# SignalRouting.net
KiCad netlist of a schematic drawn in Altium Designer
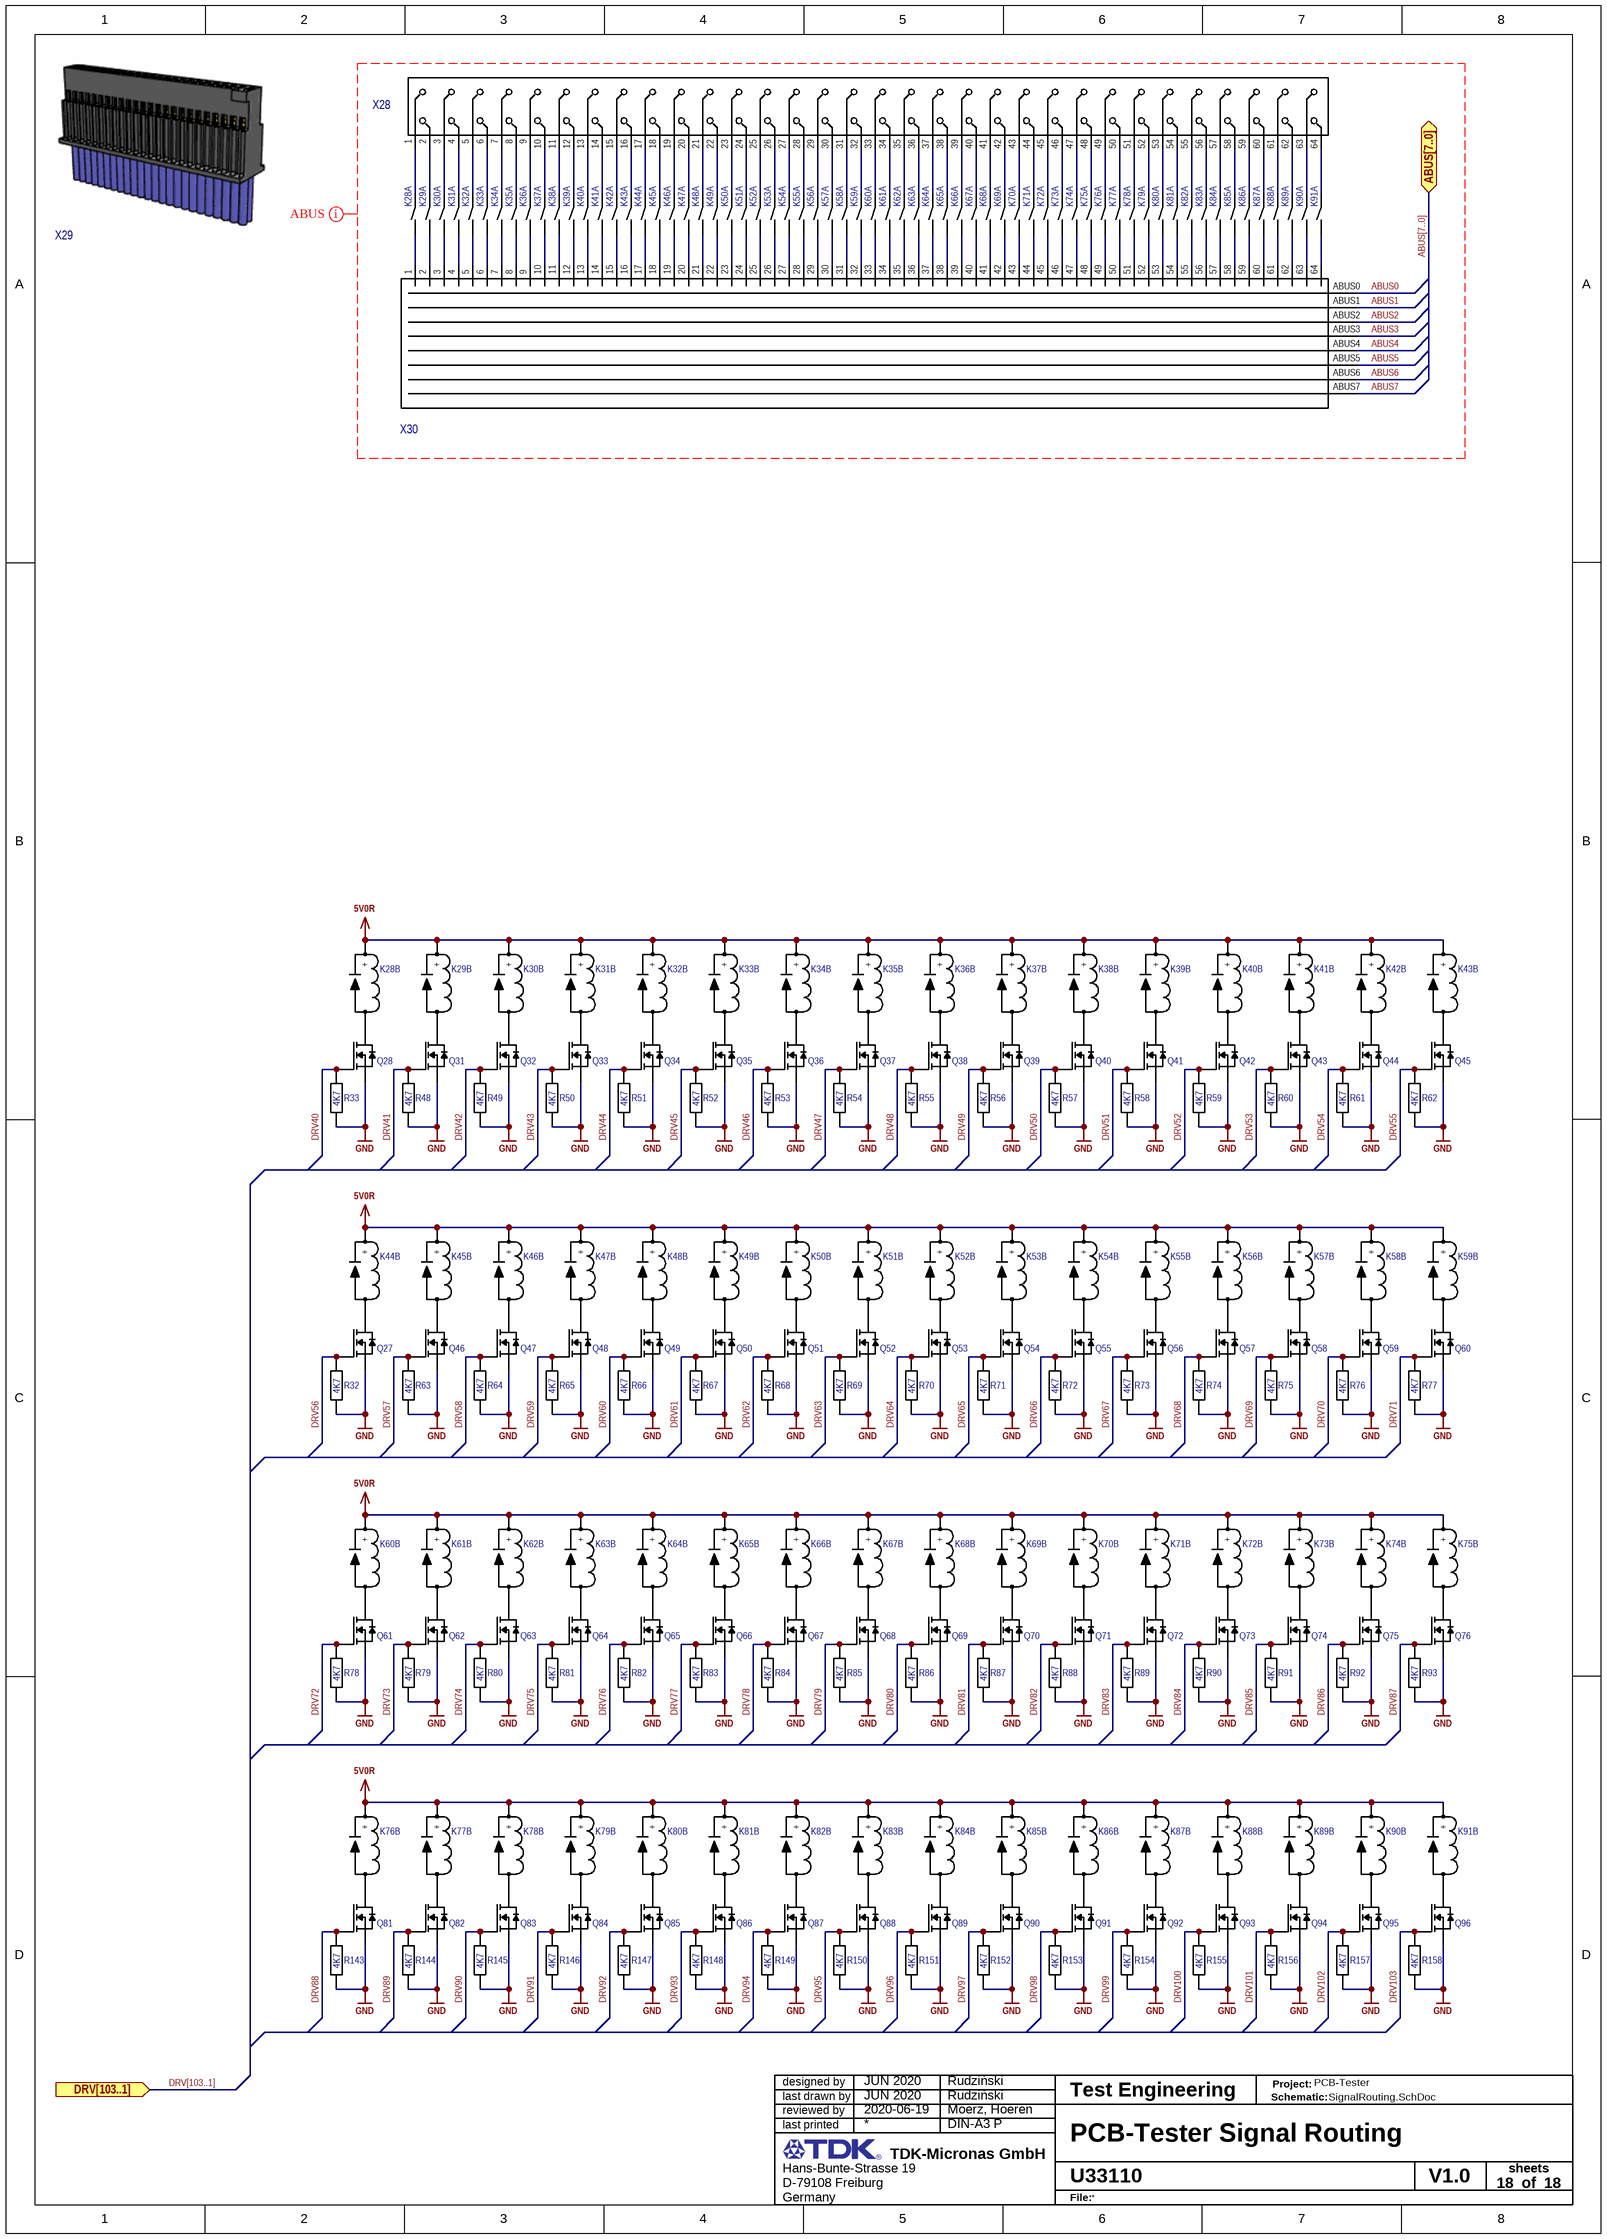
[diagram p0: SignalRouting.SchDoc]

(export (version "E")
  (design (tool "Eeschema 10.0.6"))
  (components
    (comp (ref "K28")
      (value "K")
      (footprint "118-1A")
      (description "5V Signal Relais, Normal Open")
      (fields
        (field (name "02. DISTRIBUTOR PART NUMBER") "118-1-A-5/2D")
        (field (name "13. CREATED DATE/NAME") "20.12.17 S. Kaiser")
      )
      (libsource (lib "chickenfood") (part "118-1-A-5/2D"))
    )
    (comp (ref "K29")
      (value "K")
      (footprint "118-1A")
      (description "5V Signal Relais, Normal Open")
      (fields
        (field (name "02. DISTRIBUTOR PART NUMBER") "118-1-A-5/2D")
        (field (name "13. CREATED DATE/NAME") "20.12.17 S. Kaiser")
      )
      (libsource (lib "chickenfood") (part "118-1-A-5/2D"))
    )
    (comp (ref "K30")
      (value "K")
      (footprint "118-1A")
      (description "5V Signal Relais, Normal Open")
      (fields
        (field (name "02. DISTRIBUTOR PART NUMBER") "118-1-A-5/2D")
        (field (name "13. CREATED DATE/NAME") "20.12.17 S. Kaiser")
      )
      (libsource (lib "chickenfood") (part "118-1-A-5/2D"))
    )
    (comp (ref "K31")
      (value "K")
      (footprint "118-1A")
      (description "5V Signal Relais, Normal Open")
      (fields
        (field (name "02. DISTRIBUTOR PART NUMBER") "118-1-A-5/2D")
        (field (name "13. CREATED DATE/NAME") "20.12.17 S. Kaiser")
      )
      (libsource (lib "") (part "118-1-A-5/2D_1"))
    )
    (comp (ref "K32")
      (value "K")
      (footprint "118-1A")
      (description "5V Signal Relais, Normal Open")
      (fields
        (field (name "02. DISTRIBUTOR PART NUMBER") "118-1-A-5/2D")
        (field (name "13. CREATED DATE/NAME") "20.12.17 S. Kaiser")
      )
      (libsource (lib "") (part "118-1-A-5/2D_1"))
    )
    (comp (ref "K33")
      (value "K")
      (footprint "118-1A")
      (description "5V Signal Relais, Normal Open")
      (fields
        (field (name "02. DISTRIBUTOR PART NUMBER") "118-1-A-5/2D")
        (field (name "13. CREATED DATE/NAME") "20.12.17 S. Kaiser")
      )
      (libsource (lib "") (part "118-1-A-5/2D_1"))
    )
    (comp (ref "K34")
      (value "K")
      (footprint "118-1A")
      (description "5V Signal Relais, Normal Open")
      (fields
        (field (name "02. DISTRIBUTOR PART NUMBER") "118-1-A-5/2D")
        (field (name "13. CREATED DATE/NAME") "20.12.17 S. Kaiser")
      )
      (libsource (lib "chickenfood") (part "118-1-A-5/2D"))
    )
    (comp (ref "K35")
      (value "K")
      (footprint "118-1A")
      (description "5V Signal Relais, Normal Open")
      (fields
        (field (name "02. DISTRIBUTOR PART NUMBER") "118-1-A-5/2D")
        (field (name "13. CREATED DATE/NAME") "20.12.17 S. Kaiser")
      )
      (libsource (lib "chickenfood") (part "118-1-A-5/2D"))
    )
    (comp (ref "K36")
      (value "K")
      (footprint "118-1A")
      (description "5V Signal Relais, Normal Open")
      (fields
        (field (name "02. DISTRIBUTOR PART NUMBER") "118-1-A-5/2D")
        (field (name "13. CREATED DATE/NAME") "20.12.17 S. Kaiser")
      )
      (libsource (lib "chickenfood") (part "118-1-A-5/2D"))
    )
    (comp (ref "K37")
      (value "K")
      (footprint "118-1A")
      (description "5V Signal Relais, Normal Open")
      (fields
        (field (name "02. DISTRIBUTOR PART NUMBER") "118-1-A-5/2D")
        (field (name "13. CREATED DATE/NAME") "20.12.17 S. Kaiser")
      )
      (libsource (lib "chickenfood") (part "118-1-A-5/2D"))
    )
    (comp (ref "K38")
      (value "K")
      (footprint "118-1A")
      (description "5V Signal Relais, Normal Open")
      (fields
        (field (name "02. DISTRIBUTOR PART NUMBER") "118-1-A-5/2D")
        (field (name "13. CREATED DATE/NAME") "20.12.17 S. Kaiser")
      )
      (libsource (lib "chickenfood") (part "118-1-A-5/2D"))
    )
    (comp (ref "K39")
      (value "K")
      (footprint "118-1A")
      (description "5V Signal Relais, Normal Open")
      (fields
        (field (name "02. DISTRIBUTOR PART NUMBER") "118-1-A-5/2D")
        (field (name "13. CREATED DATE/NAME") "20.12.17 S. Kaiser")
      )
      (libsource (lib "chickenfood") (part "118-1-A-5/2D"))
    )
    (comp (ref "K40")
      (value "K")
      (footprint "118-1A")
      (description "5V Signal Relais, Normal Open")
      (fields
        (field (name "02. DISTRIBUTOR PART NUMBER") "118-1-A-5/2D")
        (field (name "13. CREATED DATE/NAME") "20.12.17 S. Kaiser")
      )
      (libsource (lib "chickenfood") (part "118-1-A-5/2D"))
    )
    (comp (ref "K41")
      (value "K")
      (footprint "118-1A")
      (description "5V Signal Relais, Normal Open")
      (fields
        (field (name "02. DISTRIBUTOR PART NUMBER") "118-1-A-5/2D")
        (field (name "13. CREATED DATE/NAME") "20.12.17 S. Kaiser")
      )
      (libsource (lib "chickenfood") (part "118-1-A-5/2D"))
    )
    (comp (ref "K42")
      (value "K")
      (footprint "118-1A")
      (description "5V Signal Relais, Normal Open")
      (fields
        (field (name "02. DISTRIBUTOR PART NUMBER") "118-1-A-5/2D")
        (field (name "13. CREATED DATE/NAME") "20.12.17 S. Kaiser")
      )
      (libsource (lib "") (part "118-1-A-5/2D_1"))
    )
    (comp (ref "K43")
      (value "K")
      (footprint "118-1A")
      (description "5V Signal Relais, Normal Open")
      (fields
        (field (name "02. DISTRIBUTOR PART NUMBER") "118-1-A-5/2D")
        (field (name "13. CREATED DATE/NAME") "20.12.17 S. Kaiser")
      )
      (libsource (lib "chickenfood") (part "118-1-A-5/2D"))
    )
    (comp (ref "K44")
      (value "K")
      (footprint "118-1A")
      (description "5V Signal Relais, Normal Open")
      (fields
        (field (name "02. DISTRIBUTOR PART NUMBER") "118-1-A-5/2D")
        (field (name "13. CREATED DATE/NAME") "20.12.17 S. Kaiser")
      )
      (libsource (lib "") (part "118-1-A-5/2D_1"))
    )
    (comp (ref "K45")
      (value "K")
      (footprint "118-1A")
      (description "5V Signal Relais, Normal Open")
      (fields
        (field (name "02. DISTRIBUTOR PART NUMBER") "118-1-A-5/2D")
        (field (name "13. CREATED DATE/NAME") "20.12.17 S. Kaiser")
      )
      (libsource (lib "chickenfood") (part "118-1-A-5/2D"))
    )
    (comp (ref "K46")
      (value "K")
      (footprint "118-1A")
      (description "5V Signal Relais, Normal Open")
      (fields
        (field (name "02. DISTRIBUTOR PART NUMBER") "118-1-A-5/2D")
        (field (name "13. CREATED DATE/NAME") "20.12.17 S. Kaiser")
      )
      (libsource (lib "") (part "118-1-A-5/2D_1"))
    )
    (comp (ref "K47")
      (value "K")
      (footprint "118-1A")
      (description "5V Signal Relais, Normal Open")
      (fields
        (field (name "02. DISTRIBUTOR PART NUMBER") "118-1-A-5/2D")
        (field (name "13. CREATED DATE/NAME") "20.12.17 S. Kaiser")
      )
      (libsource (lib "chickenfood") (part "118-1-A-5/2D"))
    )
    (comp (ref "K48")
      (value "K")
      (footprint "118-1A")
      (description "5V Signal Relais, Normal Open")
      (fields
        (field (name "02. DISTRIBUTOR PART NUMBER") "118-1-A-5/2D")
        (field (name "13. CREATED DATE/NAME") "20.12.17 S. Kaiser")
      )
      (libsource (lib "") (part "118-1-A-5/2D_1"))
    )
    (comp (ref "K49")
      (value "K")
      (footprint "118-1A")
      (description "5V Signal Relais, Normal Open")
      (fields
        (field (name "02. DISTRIBUTOR PART NUMBER") "118-1-A-5/2D")
        (field (name "13. CREATED DATE/NAME") "20.12.17 S. Kaiser")
      )
      (libsource (lib "chickenfood") (part "118-1-A-5/2D"))
    )
    (comp (ref "K50")
      (value "K")
      (footprint "118-1A")
      (description "5V Signal Relais, Normal Open")
      (fields
        (field (name "02. DISTRIBUTOR PART NUMBER") "118-1-A-5/2D")
        (field (name "13. CREATED DATE/NAME") "20.12.17 S. Kaiser")
      )
      (libsource (lib "chickenfood") (part "118-1-A-5/2D"))
    )
    (comp (ref "K51")
      (value "K")
      (footprint "118-1A")
      (description "5V Signal Relais, Normal Open")
      (fields
        (field (name "02. DISTRIBUTOR PART NUMBER") "118-1-A-5/2D")
        (field (name "13. CREATED DATE/NAME") "20.12.17 S. Kaiser")
      )
      (libsource (lib "") (part "118-1-A-5/2D_1"))
    )
    (comp (ref "K52")
      (value "K")
      (footprint "118-1A")
      (description "5V Signal Relais, Normal Open")
      (fields
        (field (name "02. DISTRIBUTOR PART NUMBER") "118-1-A-5/2D")
        (field (name "13. CREATED DATE/NAME") "20.12.17 S. Kaiser")
      )
      (libsource (lib "") (part "118-1-A-5/2D_1"))
    )
    (comp (ref "K53")
      (value "K")
      (footprint "118-1A")
      (description "5V Signal Relais, Normal Open")
      (fields
        (field (name "02. DISTRIBUTOR PART NUMBER") "118-1-A-5/2D")
        (field (name "13. CREATED DATE/NAME") "20.12.17 S. Kaiser")
      )
      (libsource (lib "chickenfood") (part "118-1-A-5/2D"))
    )
    (comp (ref "K54")
      (value "K")
      (footprint "118-1A")
      (description "5V Signal Relais, Normal Open")
      (fields
        (field (name "02. DISTRIBUTOR PART NUMBER") "118-1-A-5/2D")
        (field (name "13. CREATED DATE/NAME") "20.12.17 S. Kaiser")
      )
      (libsource (lib "") (part "118-1-A-5/2D_1"))
    )
    (comp (ref "K55")
      (value "K")
      (footprint "118-1A")
      (description "5V Signal Relais, Normal Open")
      (fields
        (field (name "02. DISTRIBUTOR PART NUMBER") "118-1-A-5/2D")
        (field (name "13. CREATED DATE/NAME") "20.12.17 S. Kaiser")
      )
      (libsource (lib "chickenfood") (part "118-1-A-5/2D"))
    )
    (comp (ref "K56")
      (value "K")
      (footprint "118-1A")
      (description "5V Signal Relais, Normal Open")
      (fields
        (field (name "02. DISTRIBUTOR PART NUMBER") "118-1-A-5/2D")
        (field (name "13. CREATED DATE/NAME") "20.12.17 S. Kaiser")
      )
      (libsource (lib "") (part "118-1-A-5/2D_1"))
    )
    (comp (ref "K57")
      (value "K")
      (footprint "118-1A")
      (description "5V Signal Relais, Normal Open")
      (fields
        (field (name "02. DISTRIBUTOR PART NUMBER") "118-1-A-5/2D")
        (field (name "13. CREATED DATE/NAME") "20.12.17 S. Kaiser")
      )
      (libsource (lib "chickenfood") (part "118-1-A-5/2D"))
    )
    (comp (ref "K58")
      (value "K")
      (footprint "118-1A")
      (description "5V Signal Relais, Normal Open")
      (fields
        (field (name "02. DISTRIBUTOR PART NUMBER") "118-1-A-5/2D")
        (field (name "13. CREATED DATE/NAME") "20.12.17 S. Kaiser")
      )
      (libsource (lib "chickenfood") (part "118-1-A-5/2D"))
    )
    (comp (ref "K59")
      (value "K")
      (footprint "118-1A")
      (description "5V Signal Relais, Normal Open")
      (fields
        (field (name "02. DISTRIBUTOR PART NUMBER") "118-1-A-5/2D")
        (field (name "13. CREATED DATE/NAME") "20.12.17 S. Kaiser")
      )
      (libsource (lib "chickenfood") (part "118-1-A-5/2D"))
    )
    (comp (ref "K60")
      (value "K")
      (footprint "118-1A")
      (description "5V Signal Relais, Normal Open")
      (fields
        (field (name "02. DISTRIBUTOR PART NUMBER") "118-1-A-5/2D")
        (field (name "13. CREATED DATE/NAME") "20.12.17 S. Kaiser")
      )
      (libsource (lib "chickenfood") (part "118-1-A-5/2D"))
    )
    (comp (ref "K61")
      (value "K")
      (footprint "118-1A")
      (description "5V Signal Relais, Normal Open")
      (fields
        (field (name "02. DISTRIBUTOR PART NUMBER") "118-1-A-5/2D")
        (field (name "13. CREATED DATE/NAME") "20.12.17 S. Kaiser")
      )
      (libsource (lib "chickenfood") (part "118-1-A-5/2D"))
    )
    (comp (ref "K62")
      (value "K")
      (footprint "118-1A")
      (description "5V Signal Relais, Normal Open")
      (fields
        (field (name "02. DISTRIBUTOR PART NUMBER") "118-1-A-5/2D")
        (field (name "13. CREATED DATE/NAME") "20.12.17 S. Kaiser")
      )
      (libsource (lib "") (part "118-1-A-5/2D_1"))
    )
    (comp (ref "K63")
      (value "K")
      (footprint "118-1A")
      (description "5V Signal Relais, Normal Open")
      (fields
        (field (name "02. DISTRIBUTOR PART NUMBER") "118-1-A-5/2D")
        (field (name "13. CREATED DATE/NAME") "20.12.17 S. Kaiser")
      )
      (libsource (lib "") (part "118-1-A-5/2D_1"))
    )
    (comp (ref "K64")
      (value "K")
      (footprint "118-1A")
      (description "5V Signal Relais, Normal Open")
      (fields
        (field (name "02. DISTRIBUTOR PART NUMBER") "118-1-A-5/2D")
        (field (name "13. CREATED DATE/NAME") "20.12.17 S. Kaiser")
      )
      (libsource (lib "chickenfood") (part "118-1-A-5/2D"))
    )
    (comp (ref "K65")
      (value "K")
      (footprint "118-1A")
      (description "5V Signal Relais, Normal Open")
      (fields
        (field (name "02. DISTRIBUTOR PART NUMBER") "118-1-A-5/2D")
        (field (name "13. CREATED DATE/NAME") "20.12.17 S. Kaiser")
      )
      (libsource (lib "chickenfood") (part "118-1-A-5/2D"))
    )
    (comp (ref "K66")
      (value "K")
      (footprint "118-1A")
      (description "5V Signal Relais, Normal Open")
      (fields
        (field (name "02. DISTRIBUTOR PART NUMBER") "118-1-A-5/2D")
        (field (name "13. CREATED DATE/NAME") "20.12.17 S. Kaiser")
      )
      (libsource (lib "") (part "118-1-A-5/2D_1"))
    )
    (comp (ref "K67")
      (value "K")
      (footprint "118-1A")
      (description "5V Signal Relais, Normal Open")
      (fields
        (field (name "02. DISTRIBUTOR PART NUMBER") "118-1-A-5/2D")
        (field (name "13. CREATED DATE/NAME") "20.12.17 S. Kaiser")
      )
      (libsource (lib "") (part "118-1-A-5/2D_1"))
    )
    (comp (ref "K68")
      (value "K")
      (footprint "118-1A")
      (description "5V Signal Relais, Normal Open")
      (fields
        (field (name "02. DISTRIBUTOR PART NUMBER") "118-1-A-5/2D")
        (field (name "13. CREATED DATE/NAME") "20.12.17 S. Kaiser")
      )
      (libsource (lib "") (part "118-1-A-5/2D_1"))
    )
    (comp (ref "K69")
      (value "K")
      (footprint "118-1A")
      (description "5V Signal Relais, Normal Open")
      (fields
        (field (name "02. DISTRIBUTOR PART NUMBER") "118-1-A-5/2D")
        (field (name "13. CREATED DATE/NAME") "20.12.17 S. Kaiser")
      )
      (libsource (lib "") (part "118-1-A-5/2D_1"))
    )
    (comp (ref "K70")
      (value "K")
      (footprint "118-1A")
      (description "5V Signal Relais, Normal Open")
      (fields
        (field (name "02. DISTRIBUTOR PART NUMBER") "118-1-A-5/2D")
        (field (name "13. CREATED DATE/NAME") "20.12.17 S. Kaiser")
      )
      (libsource (lib "chickenfood") (part "118-1-A-5/2D"))
    )
    (comp (ref "K71")
      (value "K")
      (footprint "118-1A")
      (description "5V Signal Relais, Normal Open")
      (fields
        (field (name "02. DISTRIBUTOR PART NUMBER") "118-1-A-5/2D")
        (field (name "13. CREATED DATE/NAME") "20.12.17 S. Kaiser")
      )
      (libsource (lib "") (part "118-1-A-5/2D_1"))
    )
    (comp (ref "K72")
      (value "K")
      (footprint "118-1A")
      (description "5V Signal Relais, Normal Open")
      (fields
        (field (name "02. DISTRIBUTOR PART NUMBER") "118-1-A-5/2D")
        (field (name "13. CREATED DATE/NAME") "20.12.17 S. Kaiser")
      )
      (libsource (lib "chickenfood") (part "118-1-A-5/2D"))
    )
    (comp (ref "K73")
      (value "K")
      (footprint "118-1A")
      (description "5V Signal Relais, Normal Open")
      (fields
        (field (name "02. DISTRIBUTOR PART NUMBER") "118-1-A-5/2D")
        (field (name "13. CREATED DATE/NAME") "20.12.17 S. Kaiser")
      )
      (libsource (lib "chickenfood") (part "118-1-A-5/2D"))
    )
    (comp (ref "K74")
      (value "K")
      (footprint "118-1A")
      (description "5V Signal Relais, Normal Open")
      (fields
        (field (name "02. DISTRIBUTOR PART NUMBER") "118-1-A-5/2D")
        (field (name "13. CREATED DATE/NAME") "20.12.17 S. Kaiser")
      )
      (libsource (lib "chickenfood") (part "118-1-A-5/2D"))
    )
    (comp (ref "K75")
      (value "K")
      (footprint "118-1A")
      (description "5V Signal Relais, Normal Open")
      (fields
        (field (name "02. DISTRIBUTOR PART NUMBER") "118-1-A-5/2D")
        (field (name "13. CREATED DATE/NAME") "20.12.17 S. Kaiser")
      )
      (libsource (lib "") (part "118-1-A-5/2D_1"))
    )
    (comp (ref "K76")
      (value "K")
      (footprint "118-1A")
      (description "5V Signal Relais, Normal Open")
      (fields
        (field (name "02. DISTRIBUTOR PART NUMBER") "118-1-A-5/2D")
        (field (name "13. CREATED DATE/NAME") "20.12.17 S. Kaiser")
      )
      (libsource (lib "chickenfood") (part "118-1-A-5/2D"))
    )
    (comp (ref "K77")
      (value "K")
      (footprint "118-1A")
      (description "5V Signal Relais, Normal Open")
      (fields
        (field (name "02. DISTRIBUTOR PART NUMBER") "118-1-A-5/2D")
        (field (name "13. CREATED DATE/NAME") "20.12.17 S. Kaiser")
      )
      (libsource (lib "chickenfood") (part "118-1-A-5/2D"))
    )
    (comp (ref "K78")
      (value "K")
      (footprint "118-1A")
      (description "5V Signal Relais, Normal Open")
      (fields
        (field (name "02. DISTRIBUTOR PART NUMBER") "118-1-A-5/2D")
        (field (name "13. CREATED DATE/NAME") "20.12.17 S. Kaiser")
      )
      (libsource (lib "") (part "118-1-A-5/2D_1"))
    )
    (comp (ref "K79")
      (value "K")
      (footprint "118-1A")
      (description "5V Signal Relais, Normal Open")
      (fields
        (field (name "02. DISTRIBUTOR PART NUMBER") "118-1-A-5/2D")
        (field (name "13. CREATED DATE/NAME") "20.12.17 S. Kaiser")
      )
      (libsource (lib "chickenfood") (part "118-1-A-5/2D"))
    )
    (comp (ref "K80")
      (value "K")
      (footprint "118-1A")
      (description "5V Signal Relais, Normal Open")
      (fields
        (field (name "02. DISTRIBUTOR PART NUMBER") "118-1-A-5/2D")
        (field (name "13. CREATED DATE/NAME") "20.12.17 S. Kaiser")
      )
      (libsource (lib "") (part "118-1-A-5/2D_1"))
    )
    (comp (ref "K81")
      (value "K")
      (footprint "118-1A")
      (description "5V Signal Relais, Normal Open")
      (fields
        (field (name "02. DISTRIBUTOR PART NUMBER") "118-1-A-5/2D")
        (field (name "13. CREATED DATE/NAME") "20.12.17 S. Kaiser")
      )
      (libsource (lib "") (part "118-1-A-5/2D_1"))
    )
    (comp (ref "K82")
      (value "K")
      (footprint "118-1A")
      (description "5V Signal Relais, Normal Open")
      (fields
        (field (name "02. DISTRIBUTOR PART NUMBER") "118-1-A-5/2D")
        (field (name "13. CREATED DATE/NAME") "20.12.17 S. Kaiser")
      )
      (libsource (lib "") (part "118-1-A-5/2D_1"))
    )
    (comp (ref "K83")
      (value "K")
      (footprint "118-1A")
      (description "5V Signal Relais, Normal Open")
      (fields
        (field (name "02. DISTRIBUTOR PART NUMBER") "118-1-A-5/2D")
        (field (name "13. CREATED DATE/NAME") "20.12.17 S. Kaiser")
      )
      (libsource (lib "chickenfood") (part "118-1-A-5/2D"))
    )
    (comp (ref "K84")
      (value "K")
      (footprint "118-1A")
      (description "5V Signal Relais, Normal Open")
      (fields
        (field (name "02. DISTRIBUTOR PART NUMBER") "118-1-A-5/2D")
        (field (name "13. CREATED DATE/NAME") "20.12.17 S. Kaiser")
      )
      (libsource (lib "chickenfood") (part "118-1-A-5/2D"))
    )
    (comp (ref "K85")
      (value "K")
      (footprint "118-1A")
      (description "5V Signal Relais, Normal Open")
      (fields
        (field (name "02. DISTRIBUTOR PART NUMBER") "118-1-A-5/2D")
        (field (name "13. CREATED DATE/NAME") "20.12.17 S. Kaiser")
      )
      (libsource (lib "") (part "118-1-A-5/2D_1"))
    )
    (comp (ref "K86")
      (value "K")
      (footprint "118-1A")
      (description "5V Signal Relais, Normal Open")
      (fields
        (field (name "02. DISTRIBUTOR PART NUMBER") "118-1-A-5/2D")
        (field (name "13. CREATED DATE/NAME") "20.12.17 S. Kaiser")
      )
      (libsource (lib "") (part "118-1-A-5/2D_1"))
    )
    (comp (ref "K87")
      (value "K")
      (footprint "118-1A")
      (description "5V Signal Relais, Normal Open")
      (fields
        (field (name "02. DISTRIBUTOR PART NUMBER") "118-1-A-5/2D")
        (field (name "13. CREATED DATE/NAME") "20.12.17 S. Kaiser")
      )
      (libsource (lib "chickenfood") (part "118-1-A-5/2D"))
    )
    (comp (ref "K88")
      (value "K")
      (footprint "118-1A")
      (description "5V Signal Relais, Normal Open")
      (fields
        (field (name "02. DISTRIBUTOR PART NUMBER") "118-1-A-5/2D")
        (field (name "13. CREATED DATE/NAME") "20.12.17 S. Kaiser")
      )
      (libsource (lib "") (part "118-1-A-5/2D_1"))
    )
    (comp (ref "K89")
      (value "K")
      (footprint "118-1A")
      (description "5V Signal Relais, Normal Open")
      (fields
        (field (name "02. DISTRIBUTOR PART NUMBER") "118-1-A-5/2D")
        (field (name "13. CREATED DATE/NAME") "20.12.17 S. Kaiser")
      )
      (libsource (lib "") (part "118-1-A-5/2D_1"))
    )
    (comp (ref "K90")
      (value "K")
      (footprint "118-1A")
      (description "5V Signal Relais, Normal Open")
      (fields
        (field (name "02. DISTRIBUTOR PART NUMBER") "118-1-A-5/2D")
        (field (name "13. CREATED DATE/NAME") "20.12.17 S. Kaiser")
      )
      (libsource (lib "chickenfood") (part "118-1-A-5/2D"))
    )
    (comp (ref "K91")
      (value "K")
      (footprint "118-1A")
      (description "5V Signal Relais, Normal Open")
      (fields
        (field (name "02. DISTRIBUTOR PART NUMBER") "118-1-A-5/2D")
        (field (name "13. CREATED DATE/NAME") "20.12.17 S. Kaiser")
      )
      (libsource (lib "chickenfood") (part "118-1-A-5/2D"))
    )
    (comp (ref "Q27")
      (value "Q")
      (footprint "SOT23-3")
      (description "MOSFET N-CH 25V 680MA SOT-23")
      (fields
        (field (name "02. DISTRIBUTOR PART NUMBER") "FDV303NDKR-ND")
        (field (name "07. MANUFACTURER  PART NUMBER") "FDV303N")
        (field (name "13. CREATED DATE/NAME") "AUG 2018 / Hören")
      )
      (libsource (lib "SCT8-Board1") (part "FDV303N"))
    )
    (comp (ref "Q28")
      (value "Q")
      (footprint "SOT23-3")
      (description "MOSFET N-CH 25V 680MA SOT-23")
      (fields
        (field (name "02. DISTRIBUTOR PART NUMBER") "FDV303NDKR-ND")
        (field (name "07. MANUFACTURER  PART NUMBER") "FDV303N")
        (field (name "13. CREATED DATE/NAME") "AUG 2018 / Hören")
      )
      (libsource (lib "SCT8-Board1") (part "FDV303N"))
    )
    (comp (ref "Q31")
      (value "Q")
      (footprint "SOT23-3")
      (description "MOSFET N-CH 25V 680MA SOT-23")
      (fields
        (field (name "02. DISTRIBUTOR PART NUMBER") "FDV303NDKR-ND")
        (field (name "07. MANUFACTURER  PART NUMBER") "FDV303N")
        (field (name "13. CREATED DATE/NAME") "AUG 2018 / Hören")
      )
      (libsource (lib "SCT8-Board1") (part "FDV303N"))
    )
    (comp (ref "Q32")
      (value "Q")
      (footprint "SOT23-3")
      (description "MOSFET N-CH 25V 680MA SOT-23")
      (fields
        (field (name "02. DISTRIBUTOR PART NUMBER") "FDV303NDKR-ND")
        (field (name "07. MANUFACTURER  PART NUMBER") "FDV303N")
        (field (name "13. CREATED DATE/NAME") "AUG 2018 / Hören")
      )
      (libsource (lib "SCT8-Board1") (part "FDV303N"))
    )
    (comp (ref "Q33")
      (value "Q")
      (footprint "SOT23-3")
      (description "MOSFET N-CH 25V 680MA SOT-23")
      (fields
        (field (name "02. DISTRIBUTOR PART NUMBER") "FDV303NDKR-ND")
        (field (name "07. MANUFACTURER  PART NUMBER") "FDV303N")
        (field (name "13. CREATED DATE/NAME") "AUG 2018 / Hören")
      )
      (libsource (lib "SCT8-Board1") (part "FDV303N"))
    )
    (comp (ref "Q34")
      (value "Q")
      (footprint "SOT23-3")
      (description "MOSFET N-CH 25V 680MA SOT-23")
      (fields
        (field (name "02. DISTRIBUTOR PART NUMBER") "FDV303NDKR-ND")
        (field (name "07. MANUFACTURER  PART NUMBER") "FDV303N")
        (field (name "13. CREATED DATE/NAME") "AUG 2018 / Hören")
      )
      (libsource (lib "SCT8-Board1") (part "FDV303N"))
    )
    (comp (ref "Q35")
      (value "Q")
      (footprint "SOT23-3")
      (description "MOSFET N-CH 25V 680MA SOT-23")
      (fields
        (field (name "02. DISTRIBUTOR PART NUMBER") "FDV303NDKR-ND")
        (field (name "07. MANUFACTURER  PART NUMBER") "FDV303N")
        (field (name "13. CREATED DATE/NAME") "AUG 2018 / Hören")
      )
      (libsource (lib "SCT8-Board1") (part "FDV303N"))
    )
    (comp (ref "Q36")
      (value "Q")
      (footprint "SOT23-3")
      (description "MOSFET N-CH 25V 680MA SOT-23")
      (fields
        (field (name "02. DISTRIBUTOR PART NUMBER") "FDV303NDKR-ND")
        (field (name "07. MANUFACTURER  PART NUMBER") "FDV303N")
        (field (name "13. CREATED DATE/NAME") "AUG 2018 / Hören")
      )
      (libsource (lib "SCT8-Board1") (part "FDV303N"))
    )
    (comp (ref "Q37")
      (value "Q")
      (footprint "SOT23-3")
      (description "MOSFET N-CH 25V 680MA SOT-23")
      (fields
        (field (name "02. DISTRIBUTOR PART NUMBER") "FDV303NDKR-ND")
        (field (name "07. MANUFACTURER  PART NUMBER") "FDV303N")
        (field (name "13. CREATED DATE/NAME") "AUG 2018 / Hören")
      )
      (libsource (lib "SCT8-Board1") (part "FDV303N"))
    )
    (comp (ref "Q38")
      (value "Q")
      (footprint "SOT23-3")
      (description "MOSFET N-CH 25V 680MA SOT-23")
      (fields
        (field (name "02. DISTRIBUTOR PART NUMBER") "FDV303NDKR-ND")
        (field (name "07. MANUFACTURER  PART NUMBER") "FDV303N")
        (field (name "13. CREATED DATE/NAME") "AUG 2018 / Hören")
      )
      (libsource (lib "SCT8-Board1") (part "FDV303N"))
    )
    (comp (ref "Q39")
      (value "Q")
      (footprint "SOT23-3")
      (description "MOSFET N-CH 25V 680MA SOT-23")
      (fields
        (field (name "02. DISTRIBUTOR PART NUMBER") "FDV303NDKR-ND")
        (field (name "07. MANUFACTURER  PART NUMBER") "FDV303N")
        (field (name "13. CREATED DATE/NAME") "AUG 2018 / Hören")
      )
      (libsource (lib "SCT8-Board1") (part "FDV303N"))
    )
    (comp (ref "Q40")
      (value "Q")
      (footprint "SOT23-3")
      (description "MOSFET N-CH 25V 680MA SOT-23")
      (fields
        (field (name "02. DISTRIBUTOR PART NUMBER") "FDV303NDKR-ND")
        (field (name "07. MANUFACTURER  PART NUMBER") "FDV303N")
        (field (name "13. CREATED DATE/NAME") "AUG 2018 / Hören")
      )
      (libsource (lib "SCT8-Board1") (part "FDV303N"))
    )
    (comp (ref "Q41")
      (value "Q")
      (footprint "SOT23-3")
      (description "MOSFET N-CH 25V 680MA SOT-23")
      (fields
        (field (name "02. DISTRIBUTOR PART NUMBER") "FDV303NDKR-ND")
        (field (name "07. MANUFACTURER  PART NUMBER") "FDV303N")
        (field (name "13. CREATED DATE/NAME") "AUG 2018 / Hören")
      )
      (libsource (lib "SCT8-Board1") (part "FDV303N"))
    )
    (comp (ref "Q42")
      (value "Q")
      (footprint "SOT23-3")
      (description "MOSFET N-CH 25V 680MA SOT-23")
      (fields
        (field (name "02. DISTRIBUTOR PART NUMBER") "FDV303NDKR-ND")
        (field (name "07. MANUFACTURER  PART NUMBER") "FDV303N")
        (field (name "13. CREATED DATE/NAME") "AUG 2018 / Hören")
      )
      (libsource (lib "SCT8-Board1") (part "FDV303N"))
    )
    (comp (ref "Q43")
      (value "Q")
      (footprint "SOT23-3")
      (description "MOSFET N-CH 25V 680MA SOT-23")
      (fields
        (field (name "02. DISTRIBUTOR PART NUMBER") "FDV303NDKR-ND")
        (field (name "07. MANUFACTURER  PART NUMBER") "FDV303N")
        (field (name "13. CREATED DATE/NAME") "AUG 2018 / Hören")
      )
      (libsource (lib "SCT8-Board1") (part "FDV303N"))
    )
    (comp (ref "Q44")
      (value "Q")
      (footprint "SOT23-3")
      (description "MOSFET N-CH 25V 680MA SOT-23")
      (fields
        (field (name "02. DISTRIBUTOR PART NUMBER") "FDV303NDKR-ND")
        (field (name "07. MANUFACTURER  PART NUMBER") "FDV303N")
        (field (name "13. CREATED DATE/NAME") "AUG 2018 / Hören")
      )
      (libsource (lib "SCT8-Board1") (part "FDV303N"))
    )
    (comp (ref "Q45")
      (value "Q")
      (footprint "SOT23-3")
      (description "MOSFET N-CH 25V 680MA SOT-23")
      (fields
        (field (name "02. DISTRIBUTOR PART NUMBER") "FDV303NDKR-ND")
        (field (name "07. MANUFACTURER  PART NUMBER") "FDV303N")
        (field (name "13. CREATED DATE/NAME") "AUG 2018 / Hören")
      )
      (libsource (lib "SCT8-Board1") (part "FDV303N"))
    )
    (comp (ref "Q46")
      (value "Q")
      (footprint "SOT23-3")
      (description "MOSFET N-CH 25V 680MA SOT-23")
      (fields
        (field (name "02. DISTRIBUTOR PART NUMBER") "FDV303NDKR-ND")
        (field (name "07. MANUFACTURER  PART NUMBER") "FDV303N")
        (field (name "13. CREATED DATE/NAME") "AUG 2018 / Hören")
      )
      (libsource (lib "SCT8-Board1") (part "FDV303N"))
    )
    (comp (ref "Q47")
      (value "Q")
      (footprint "SOT23-3")
      (description "MOSFET N-CH 25V 680MA SOT-23")
      (fields
        (field (name "02. DISTRIBUTOR PART NUMBER") "FDV303NDKR-ND")
        (field (name "07. MANUFACTURER  PART NUMBER") "FDV303N")
        (field (name "13. CREATED DATE/NAME") "AUG 2018 / Hören")
      )
      (libsource (lib "SCT8-Board1") (part "FDV303N"))
    )
    (comp (ref "Q48")
      (value "Q")
      (footprint "SOT23-3")
      (description "MOSFET N-CH 25V 680MA SOT-23")
      (fields
        (field (name "02. DISTRIBUTOR PART NUMBER") "FDV303NDKR-ND")
        (field (name "07. MANUFACTURER  PART NUMBER") "FDV303N")
        (field (name "13. CREATED DATE/NAME") "AUG 2018 / Hören")
      )
      (libsource (lib "SCT8-Board1") (part "FDV303N"))
    )
    (comp (ref "Q49")
      (value "Q")
      (footprint "SOT23-3")
      (description "MOSFET N-CH 25V 680MA SOT-23")
      (fields
        (field (name "02. DISTRIBUTOR PART NUMBER") "FDV303NDKR-ND")
        (field (name "07. MANUFACTURER  PART NUMBER") "FDV303N")
        (field (name "13. CREATED DATE/NAME") "AUG 2018 / Hören")
      )
      (libsource (lib "SCT8-Board1") (part "FDV303N"))
    )
    (comp (ref "Q50")
      (value "Q")
      (footprint "SOT23-3")
      (description "MOSFET N-CH 25V 680MA SOT-23")
      (fields
        (field (name "02. DISTRIBUTOR PART NUMBER") "FDV303NDKR-ND")
        (field (name "07. MANUFACTURER  PART NUMBER") "FDV303N")
        (field (name "13. CREATED DATE/NAME") "AUG 2018 / Hören")
      )
      (libsource (lib "SCT8-Board1") (part "FDV303N"))
    )
    (comp (ref "Q51")
      (value "Q")
      (footprint "SOT23-3")
      (description "MOSFET N-CH 25V 680MA SOT-23")
      (fields
        (field (name "02. DISTRIBUTOR PART NUMBER") "FDV303NDKR-ND")
        (field (name "07. MANUFACTURER  PART NUMBER") "FDV303N")
        (field (name "13. CREATED DATE/NAME") "AUG 2018 / Hören")
      )
      (libsource (lib "SCT8-Board1") (part "FDV303N"))
    )
    (comp (ref "Q52")
      (value "Q")
      (footprint "SOT23-3")
      (description "MOSFET N-CH 25V 680MA SOT-23")
      (fields
        (field (name "02. DISTRIBUTOR PART NUMBER") "FDV303NDKR-ND")
        (field (name "07. MANUFACTURER  PART NUMBER") "FDV303N")
        (field (name "13. CREATED DATE/NAME") "AUG 2018 / Hören")
      )
      (libsource (lib "SCT8-Board1") (part "FDV303N"))
    )
    (comp (ref "Q53")
      (value "Q")
      (footprint "SOT23-3")
      (description "MOSFET N-CH 25V 680MA SOT-23")
      (fields
        (field (name "02. DISTRIBUTOR PART NUMBER") "FDV303NDKR-ND")
        (field (name "07. MANUFACTURER  PART NUMBER") "FDV303N")
        (field (name "13. CREATED DATE/NAME") "AUG 2018 / Hören")
      )
      (libsource (lib "SCT8-Board1") (part "FDV303N"))
    )
    (comp (ref "Q54")
      (value "Q")
      (footprint "SOT23-3")
      (description "MOSFET N-CH 25V 680MA SOT-23")
      (fields
        (field (name "02. DISTRIBUTOR PART NUMBER") "FDV303NDKR-ND")
        (field (name "07. MANUFACTURER  PART NUMBER") "FDV303N")
        (field (name "13. CREATED DATE/NAME") "AUG 2018 / Hören")
      )
      (libsource (lib "SCT8-Board1") (part "FDV303N"))
    )
    (comp (ref "Q55")
      (value "Q")
      (footprint "SOT23-3")
      (description "MOSFET N-CH 25V 680MA SOT-23")
      (fields
        (field (name "02. DISTRIBUTOR PART NUMBER") "FDV303NDKR-ND")
        (field (name "07. MANUFACTURER  PART NUMBER") "FDV303N")
        (field (name "13. CREATED DATE/NAME") "AUG 2018 / Hören")
      )
      (libsource (lib "SCT8-Board1") (part "FDV303N"))
    )
    (comp (ref "Q56")
      (value "Q")
      (footprint "SOT23-3")
      (description "MOSFET N-CH 25V 680MA SOT-23")
      (fields
        (field (name "02. DISTRIBUTOR PART NUMBER") "FDV303NDKR-ND")
        (field (name "07. MANUFACTURER  PART NUMBER") "FDV303N")
        (field (name "13. CREATED DATE/NAME") "AUG 2018 / Hören")
      )
      (libsource (lib "SCT8-Board1") (part "FDV303N"))
    )
    (comp (ref "Q57")
      (value "Q")
      (footprint "SOT23-3")
      (description "MOSFET N-CH 25V 680MA SOT-23")
      (fields
        (field (name "02. DISTRIBUTOR PART NUMBER") "FDV303NDKR-ND")
        (field (name "07. MANUFACTURER  PART NUMBER") "FDV303N")
        (field (name "13. CREATED DATE/NAME") "AUG 2018 / Hören")
      )
      (libsource (lib "SCT8-Board1") (part "FDV303N"))
    )
    (comp (ref "Q58")
      (value "Q")
      (footprint "SOT23-3")
      (description "MOSFET N-CH 25V 680MA SOT-23")
      (fields
        (field (name "02. DISTRIBUTOR PART NUMBER") "FDV303NDKR-ND")
        (field (name "07. MANUFACTURER  PART NUMBER") "FDV303N")
        (field (name "13. CREATED DATE/NAME") "AUG 2018 / Hören")
      )
      (libsource (lib "SCT8-Board1") (part "FDV303N"))
    )
    (comp (ref "Q59")
      (value "Q")
      (footprint "SOT23-3")
      (description "MOSFET N-CH 25V 680MA SOT-23")
      (fields
        (field (name "02. DISTRIBUTOR PART NUMBER") "FDV303NDKR-ND")
        (field (name "07. MANUFACTURER  PART NUMBER") "FDV303N")
        (field (name "13. CREATED DATE/NAME") "AUG 2018 / Hören")
      )
      (libsource (lib "SCT8-Board1") (part "FDV303N"))
    )
    (comp (ref "Q60")
      (value "Q")
      (footprint "SOT23-3")
      (description "MOSFET N-CH 25V 680MA SOT-23")
      (fields
        (field (name "02. DISTRIBUTOR PART NUMBER") "FDV303NDKR-ND")
        (field (name "07. MANUFACTURER  PART NUMBER") "FDV303N")
        (field (name "13. CREATED DATE/NAME") "AUG 2018 / Hören")
      )
      (libsource (lib "SCT8-Board1") (part "FDV303N"))
    )
    (comp (ref "Q61")
      (value "Q")
      (footprint "SOT23-3")
      (description "MOSFET N-CH 25V 680MA SOT-23")
      (fields
        (field (name "02. DISTRIBUTOR PART NUMBER") "FDV303NDKR-ND")
        (field (name "07. MANUFACTURER  PART NUMBER") "FDV303N")
        (field (name "13. CREATED DATE/NAME") "AUG 2018 / Hören")
      )
      (libsource (lib "SCT8-Board1") (part "FDV303N"))
    )
    (comp (ref "Q62")
      (value "Q")
      (footprint "SOT23-3")
      (description "MOSFET N-CH 25V 680MA SOT-23")
      (fields
        (field (name "02. DISTRIBUTOR PART NUMBER") "FDV303NDKR-ND")
        (field (name "07. MANUFACTURER  PART NUMBER") "FDV303N")
        (field (name "13. CREATED DATE/NAME") "AUG 2018 / Hören")
      )
      (libsource (lib "SCT8-Board1") (part "FDV303N"))
    )
    (comp (ref "Q63")
      (value "Q")
      (footprint "SOT23-3")
      (description "MOSFET N-CH 25V 680MA SOT-23")
      (fields
        (field (name "02. DISTRIBUTOR PART NUMBER") "FDV303NDKR-ND")
        (field (name "07. MANUFACTURER  PART NUMBER") "FDV303N")
        (field (name "13. CREATED DATE/NAME") "AUG 2018 / Hören")
      )
      (libsource (lib "SCT8-Board1") (part "FDV303N"))
    )
    (comp (ref "Q64")
      (value "Q")
      (footprint "SOT23-3")
      (description "MOSFET N-CH 25V 680MA SOT-23")
      (fields
        (field (name "02. DISTRIBUTOR PART NUMBER") "FDV303NDKR-ND")
        (field (name "07. MANUFACTURER  PART NUMBER") "FDV303N")
        (field (name "13. CREATED DATE/NAME") "AUG 2018 / Hören")
      )
      (libsource (lib "SCT8-Board1") (part "FDV303N"))
    )
    (comp (ref "Q65")
      (value "Q")
      (footprint "SOT23-3")
      (description "MOSFET N-CH 25V 680MA SOT-23")
      (fields
        (field (name "02. DISTRIBUTOR PART NUMBER") "FDV303NDKR-ND")
        (field (name "07. MANUFACTURER  PART NUMBER") "FDV303N")
        (field (name "13. CREATED DATE/NAME") "AUG 2018 / Hören")
      )
      (libsource (lib "SCT8-Board1") (part "FDV303N"))
    )
    (comp (ref "Q66")
      (value "Q")
      (footprint "SOT23-3")
      (description "MOSFET N-CH 25V 680MA SOT-23")
      (fields
        (field (name "02. DISTRIBUTOR PART NUMBER") "FDV303NDKR-ND")
        (field (name "07. MANUFACTURER  PART NUMBER") "FDV303N")
        (field (name "13. CREATED DATE/NAME") "AUG 2018 / Hören")
      )
      (libsource (lib "SCT8-Board1") (part "FDV303N"))
    )
    (comp (ref "Q67")
      (value "Q")
      (footprint "SOT23-3")
      (description "MOSFET N-CH 25V 680MA SOT-23")
      (fields
        (field (name "02. DISTRIBUTOR PART NUMBER") "FDV303NDKR-ND")
        (field (name "07. MANUFACTURER  PART NUMBER") "FDV303N")
        (field (name "13. CREATED DATE/NAME") "AUG 2018 / Hören")
      )
      (libsource (lib "SCT8-Board1") (part "FDV303N"))
    )
    (comp (ref "Q68")
      (value "Q")
      (footprint "SOT23-3")
      (description "MOSFET N-CH 25V 680MA SOT-23")
      (fields
        (field (name "02. DISTRIBUTOR PART NUMBER") "FDV303NDKR-ND")
        (field (name "07. MANUFACTURER  PART NUMBER") "FDV303N")
        (field (name "13. CREATED DATE/NAME") "AUG 2018 / Hören")
      )
      (libsource (lib "SCT8-Board1") (part "FDV303N"))
    )
    (comp (ref "Q69")
      (value "Q")
      (footprint "SOT23-3")
      (description "MOSFET N-CH 25V 680MA SOT-23")
      (fields
        (field (name "02. DISTRIBUTOR PART NUMBER") "FDV303NDKR-ND")
        (field (name "07. MANUFACTURER  PART NUMBER") "FDV303N")
        (field (name "13. CREATED DATE/NAME") "AUG 2018 / Hören")
      )
      (libsource (lib "SCT8-Board1") (part "FDV303N"))
    )
    (comp (ref "Q70")
      (value "Q")
      (footprint "SOT23-3")
      (description "MOSFET N-CH 25V 680MA SOT-23")
      (fields
        (field (name "02. DISTRIBUTOR PART NUMBER") "FDV303NDKR-ND")
        (field (name "07. MANUFACTURER  PART NUMBER") "FDV303N")
        (field (name "13. CREATED DATE/NAME") "AUG 2018 / Hören")
      )
      (libsource (lib "SCT8-Board1") (part "FDV303N"))
    )
    (comp (ref "Q71")
      (value "Q")
      (footprint "SOT23-3")
      (description "MOSFET N-CH 25V 680MA SOT-23")
      (fields
        (field (name "02. DISTRIBUTOR PART NUMBER") "FDV303NDKR-ND")
        (field (name "07. MANUFACTURER  PART NUMBER") "FDV303N")
        (field (name "13. CREATED DATE/NAME") "AUG 2018 / Hören")
      )
      (libsource (lib "SCT8-Board1") (part "FDV303N"))
    )
    (comp (ref "Q72")
      (value "Q")
      (footprint "SOT23-3")
      (description "MOSFET N-CH 25V 680MA SOT-23")
      (fields
        (field (name "02. DISTRIBUTOR PART NUMBER") "FDV303NDKR-ND")
        (field (name "07. MANUFACTURER  PART NUMBER") "FDV303N")
        (field (name "13. CREATED DATE/NAME") "AUG 2018 / Hören")
      )
      (libsource (lib "SCT8-Board1") (part "FDV303N"))
    )
    (comp (ref "Q73")
      (value "Q")
      (footprint "SOT23-3")
      (description "MOSFET N-CH 25V 680MA SOT-23")
      (fields
        (field (name "02. DISTRIBUTOR PART NUMBER") "FDV303NDKR-ND")
        (field (name "07. MANUFACTURER  PART NUMBER") "FDV303N")
        (field (name "13. CREATED DATE/NAME") "AUG 2018 / Hören")
      )
      (libsource (lib "SCT8-Board1") (part "FDV303N"))
    )
    (comp (ref "Q74")
      (value "Q")
      (footprint "SOT23-3")
      (description "MOSFET N-CH 25V 680MA SOT-23")
      (fields
        (field (name "02. DISTRIBUTOR PART NUMBER") "FDV303NDKR-ND")
        (field (name "07. MANUFACTURER  PART NUMBER") "FDV303N")
        (field (name "13. CREATED DATE/NAME") "AUG 2018 / Hören")
      )
      (libsource (lib "SCT8-Board1") (part "FDV303N"))
    )
    (comp (ref "Q75")
      (value "Q")
      (footprint "SOT23-3")
      (description "MOSFET N-CH 25V 680MA SOT-23")
      (fields
        (field (name "02. DISTRIBUTOR PART NUMBER") "FDV303NDKR-ND")
        (field (name "07. MANUFACTURER  PART NUMBER") "FDV303N")
        (field (name "13. CREATED DATE/NAME") "AUG 2018 / Hören")
      )
      (libsource (lib "SCT8-Board1") (part "FDV303N"))
    )
    (comp (ref "Q76")
      (value "Q")
      (footprint "SOT23-3")
      (description "MOSFET N-CH 25V 680MA SOT-23")
      (fields
        (field (name "02. DISTRIBUTOR PART NUMBER") "FDV303NDKR-ND")
        (field (name "07. MANUFACTURER  PART NUMBER") "FDV303N")
        (field (name "13. CREATED DATE/NAME") "AUG 2018 / Hören")
      )
      (libsource (lib "SCT8-Board1") (part "FDV303N"))
    )
    (comp (ref "Q81")
      (value "Q")
      (footprint "SOT23-3")
      (description "MOSFET N-CH 25V 680MA SOT-23")
      (fields
        (field (name "02. DISTRIBUTOR PART NUMBER") "FDV303NDKR-ND")
        (field (name "07. MANUFACTURER  PART NUMBER") "FDV303N")
        (field (name "13. CREATED DATE/NAME") "AUG 2018 / Hören")
      )
      (libsource (lib "SCT8-Board1") (part "FDV303N"))
    )
    (comp (ref "Q82")
      (value "Q")
      (footprint "SOT23-3")
      (description "MOSFET N-CH 25V 680MA SOT-23")
      (fields
        (field (name "02. DISTRIBUTOR PART NUMBER") "FDV303NDKR-ND")
        (field (name "07. MANUFACTURER  PART NUMBER") "FDV303N")
        (field (name "13. CREATED DATE/NAME") "AUG 2018 / Hören")
      )
      (libsource (lib "SCT8-Board1") (part "FDV303N"))
    )
    (comp (ref "Q83")
      (value "Q")
      (footprint "SOT23-3")
      (description "MOSFET N-CH 25V 680MA SOT-23")
      (fields
        (field (name "02. DISTRIBUTOR PART NUMBER") "FDV303NDKR-ND")
        (field (name "07. MANUFACTURER  PART NUMBER") "FDV303N")
        (field (name "13. CREATED DATE/NAME") "AUG 2018 / Hören")
      )
      (libsource (lib "SCT8-Board1") (part "FDV303N"))
    )
    (comp (ref "Q84")
      (value "Q")
      (footprint "SOT23-3")
      (description "MOSFET N-CH 25V 680MA SOT-23")
      (fields
        (field (name "02. DISTRIBUTOR PART NUMBER") "FDV303NDKR-ND")
        (field (name "07. MANUFACTURER  PART NUMBER") "FDV303N")
        (field (name "13. CREATED DATE/NAME") "AUG 2018 / Hören")
      )
      (libsource (lib "SCT8-Board1") (part "FDV303N"))
    )
    (comp (ref "Q85")
      (value "Q")
      (footprint "SOT23-3")
      (description "MOSFET N-CH 25V 680MA SOT-23")
      (fields
        (field (name "02. DISTRIBUTOR PART NUMBER") "FDV303NDKR-ND")
        (field (name "07. MANUFACTURER  PART NUMBER") "FDV303N")
        (field (name "13. CREATED DATE/NAME") "AUG 2018 / Hören")
      )
      (libsource (lib "SCT8-Board1") (part "FDV303N"))
    )
    (comp (ref "Q86")
      (value "Q")
      (footprint "SOT23-3")
      (description "MOSFET N-CH 25V 680MA SOT-23")
      (fields
        (field (name "02. DISTRIBUTOR PART NUMBER") "FDV303NDKR-ND")
        (field (name "07. MANUFACTURER  PART NUMBER") "FDV303N")
        (field (name "13. CREATED DATE/NAME") "AUG 2018 / Hören")
      )
      (libsource (lib "SCT8-Board1") (part "FDV303N"))
    )
    (comp (ref "Q87")
      (value "Q")
      (footprint "SOT23-3")
      (description "MOSFET N-CH 25V 680MA SOT-23")
      (fields
        (field (name "02. DISTRIBUTOR PART NUMBER") "FDV303NDKR-ND")
        (field (name "07. MANUFACTURER  PART NUMBER") "FDV303N")
        (field (name "13. CREATED DATE/NAME") "AUG 2018 / Hören")
      )
      (libsource (lib "SCT8-Board1") (part "FDV303N"))
    )
    (comp (ref "Q88")
      (value "Q")
      (footprint "SOT23-3")
      (description "MOSFET N-CH 25V 680MA SOT-23")
      (fields
        (field (name "02. DISTRIBUTOR PART NUMBER") "FDV303NDKR-ND")
        (field (name "07. MANUFACTURER  PART NUMBER") "FDV303N")
        (field (name "13. CREATED DATE/NAME") "AUG 2018 / Hören")
      )
      (libsource (lib "SCT8-Board1") (part "FDV303N"))
    )
    (comp (ref "Q89")
      (value "Q")
      (footprint "SOT23-3")
      (description "MOSFET N-CH 25V 680MA SOT-23")
      (fields
        (field (name "02. DISTRIBUTOR PART NUMBER") "FDV303NDKR-ND")
        (field (name "07. MANUFACTURER  PART NUMBER") "FDV303N")
        (field (name "13. CREATED DATE/NAME") "AUG 2018 / Hören")
      )
      (libsource (lib "SCT8-Board1") (part "FDV303N"))
    )
    (comp (ref "Q90")
      (value "Q")
      (footprint "SOT23-3")
      (description "MOSFET N-CH 25V 680MA SOT-23")
      (fields
        (field (name "02. DISTRIBUTOR PART NUMBER") "FDV303NDKR-ND")
        (field (name "07. MANUFACTURER  PART NUMBER") "FDV303N")
        (field (name "13. CREATED DATE/NAME") "AUG 2018 / Hören")
      )
      (libsource (lib "SCT8-Board1") (part "FDV303N"))
    )
    (comp (ref "Q91")
      (value "Q")
      (footprint "SOT23-3")
      (description "MOSFET N-CH 25V 680MA SOT-23")
      (fields
        (field (name "02. DISTRIBUTOR PART NUMBER") "FDV303NDKR-ND")
        (field (name "07. MANUFACTURER  PART NUMBER") "FDV303N")
        (field (name "13. CREATED DATE/NAME") "AUG 2018 / Hören")
      )
      (libsource (lib "SCT8-Board1") (part "FDV303N"))
    )
    (comp (ref "Q92")
      (value "Q")
      (footprint "SOT23-3")
      (description "MOSFET N-CH 25V 680MA SOT-23")
      (fields
        (field (name "02. DISTRIBUTOR PART NUMBER") "FDV303NDKR-ND")
        (field (name "07. MANUFACTURER  PART NUMBER") "FDV303N")
        (field (name "13. CREATED DATE/NAME") "AUG 2018 / Hören")
      )
      (libsource (lib "SCT8-Board1") (part "FDV303N"))
    )
    (comp (ref "Q93")
      (value "Q")
      (footprint "SOT23-3")
      (description "MOSFET N-CH 25V 680MA SOT-23")
      (fields
        (field (name "02. DISTRIBUTOR PART NUMBER") "FDV303NDKR-ND")
        (field (name "07. MANUFACTURER  PART NUMBER") "FDV303N")
        (field (name "13. CREATED DATE/NAME") "AUG 2018 / Hören")
      )
      (libsource (lib "SCT8-Board1") (part "FDV303N"))
    )
    (comp (ref "Q94")
      (value "Q")
      (footprint "SOT23-3")
      (description "MOSFET N-CH 25V 680MA SOT-23")
      (fields
        (field (name "02. DISTRIBUTOR PART NUMBER") "FDV303NDKR-ND")
        (field (name "07. MANUFACTURER  PART NUMBER") "FDV303N")
        (field (name "13. CREATED DATE/NAME") "AUG 2018 / Hören")
      )
      (libsource (lib "SCT8-Board1") (part "FDV303N"))
    )
    (comp (ref "Q95")
      (value "Q")
      (footprint "SOT23-3")
      (description "MOSFET N-CH 25V 680MA SOT-23")
      (fields
        (field (name "02. DISTRIBUTOR PART NUMBER") "FDV303NDKR-ND")
        (field (name "07. MANUFACTURER  PART NUMBER") "FDV303N")
        (field (name "13. CREATED DATE/NAME") "AUG 2018 / Hören")
      )
      (libsource (lib "SCT8-Board1") (part "FDV303N"))
    )
    (comp (ref "Q96")
      (value "Q")
      (footprint "SOT23-3")
      (description "MOSFET N-CH 25V 680MA SOT-23")
      (fields
        (field (name "02. DISTRIBUTOR PART NUMBER") "FDV303NDKR-ND")
        (field (name "07. MANUFACTURER  PART NUMBER") "FDV303N")
        (field (name "13. CREATED DATE/NAME") "AUG 2018 / Hören")
      )
      (libsource (lib "SCT8-Board1") (part "FDV303N"))
    )
    (comp (ref "R32")
      (value "4K7")
      (footprint "R0603 Reflow")
      (description "RES SMD 4.7K OHM 1% 1/10W 0603")
      (fields
        (field (name "TOLERANCE") "±1%")
        (field (name "02. DISTRIBUTOR PART NUMBER") "311-4.70KHRCT-ND")
        (field (name "13. CREATED DATE/NAME") "AUG2018/Hören")
      )
      (libsource (lib "chickenfood") (part "R"))
    )
    (comp (ref "R33")
      (value "4K7")
      (footprint "R0603 Reflow")
      (description "RES SMD 4.7K OHM 1% 1/10W 0603")
      (fields
        (field (name "TOLERANCE") "±1%")
        (field (name "02. DISTRIBUTOR PART NUMBER") "311-4.70KHRCT-ND")
        (field (name "13. CREATED DATE/NAME") "AUG2018/Hören")
      )
      (libsource (lib "chickenfood") (part "R"))
    )
    (comp (ref "R48")
      (value "4K7")
      (footprint "R0603 Reflow")
      (description "RES SMD 4.7K OHM 1% 1/10W 0603")
      (fields
        (field (name "TOLERANCE") "±1%")
        (field (name "02. DISTRIBUTOR PART NUMBER") "311-4.70KHRCT-ND")
        (field (name "13. CREATED DATE/NAME") "AUG2018/Hören")
      )
      (libsource (lib "chickenfood") (part "R"))
    )
    (comp (ref "R49")
      (value "4K7")
      (footprint "R0603 Reflow")
      (description "RES SMD 4.7K OHM 1% 1/10W 0603")
      (fields
        (field (name "TOLERANCE") "±1%")
        (field (name "02. DISTRIBUTOR PART NUMBER") "311-4.70KHRCT-ND")
        (field (name "13. CREATED DATE/NAME") "AUG2018/Hören")
      )
      (libsource (lib "chickenfood") (part "R"))
    )
    (comp (ref "R50")
      (value "4K7")
      (footprint "R0603 Reflow")
      (description "RES SMD 4.7K OHM 1% 1/10W 0603")
      (fields
        (field (name "TOLERANCE") "±1%")
        (field (name "02. DISTRIBUTOR PART NUMBER") "311-4.70KHRCT-ND")
        (field (name "13. CREATED DATE/NAME") "AUG2018/Hören")
      )
      (libsource (lib "chickenfood") (part "R"))
    )
    (comp (ref "R51")
      (value "4K7")
      (footprint "R0603 Reflow")
      (description "RES SMD 4.7K OHM 1% 1/10W 0603")
      (fields
        (field (name "TOLERANCE") "±1%")
        (field (name "02. DISTRIBUTOR PART NUMBER") "311-4.70KHRCT-ND")
        (field (name "13. CREATED DATE/NAME") "AUG2018/Hören")
      )
      (libsource (lib "chickenfood") (part "R"))
    )
    (comp (ref "R52")
      (value "4K7")
      (footprint "R0603 Reflow")
      (description "RES SMD 4.7K OHM 1% 1/10W 0603")
      (fields
        (field (name "TOLERANCE") "±1%")
        (field (name "02. DISTRIBUTOR PART NUMBER") "311-4.70KHRCT-ND")
        (field (name "13. CREATED DATE/NAME") "AUG2018/Hören")
      )
      (libsource (lib "chickenfood") (part "R"))
    )
    (comp (ref "R53")
      (value "4K7")
      (footprint "R0603 Reflow")
      (description "RES SMD 4.7K OHM 1% 1/10W 0603")
      (fields
        (field (name "TOLERANCE") "±1%")
        (field (name "02. DISTRIBUTOR PART NUMBER") "311-4.70KHRCT-ND")
        (field (name "13. CREATED DATE/NAME") "AUG2018/Hören")
      )
      (libsource (lib "chickenfood") (part "R"))
    )
    (comp (ref "R54")
      (value "4K7")
      (footprint "R0603 Reflow")
      (description "RES SMD 4.7K OHM 1% 1/10W 0603")
      (fields
        (field (name "TOLERANCE") "±1%")
        (field (name "02. DISTRIBUTOR PART NUMBER") "311-4.70KHRCT-ND")
        (field (name "13. CREATED DATE/NAME") "AUG2018/Hören")
      )
      (libsource (lib "chickenfood") (part "R"))
    )
    (comp (ref "R55")
      (value "4K7")
      (footprint "R0603 Reflow")
      (description "RES SMD 4.7K OHM 1% 1/10W 0603")
      (fields
        (field (name "TOLERANCE") "±1%")
        (field (name "02. DISTRIBUTOR PART NUMBER") "311-4.70KHRCT-ND")
        (field (name "13. CREATED DATE/NAME") "AUG2018/Hören")
      )
      (libsource (lib "chickenfood") (part "R"))
    )
    (comp (ref "R56")
      (value "4K7")
      (footprint "R0603 Reflow")
      (description "RES SMD 4.7K OHM 1% 1/10W 0603")
      (fields
        (field (name "TOLERANCE") "±1%")
        (field (name "02. DISTRIBUTOR PART NUMBER") "311-4.70KHRCT-ND")
        (field (name "13. CREATED DATE/NAME") "AUG2018/Hören")
      )
      (libsource (lib "chickenfood") (part "R"))
    )
    (comp (ref "R57")
      (value "4K7")
      (footprint "R0603 Reflow")
      (description "RES SMD 4.7K OHM 1% 1/10W 0603")
      (fields
        (field (name "TOLERANCE") "±1%")
        (field (name "02. DISTRIBUTOR PART NUMBER") "311-4.70KHRCT-ND")
        (field (name "13. CREATED DATE/NAME") "AUG2018/Hören")
      )
      (libsource (lib "chickenfood") (part "R"))
    )
    (comp (ref "R58")
      (value "4K7")
      (footprint "R0603 Reflow")
      (description "RES SMD 4.7K OHM 1% 1/10W 0603")
      (fields
        (field (name "TOLERANCE") "±1%")
        (field (name "02. DISTRIBUTOR PART NUMBER") "311-4.70KHRCT-ND")
        (field (name "13. CREATED DATE/NAME") "AUG2018/Hören")
      )
      (libsource (lib "chickenfood") (part "R"))
    )
    (comp (ref "R59")
      (value "4K7")
      (footprint "R0603 Reflow")
      (description "RES SMD 4.7K OHM 1% 1/10W 0603")
      (fields
        (field (name "TOLERANCE") "±1%")
        (field (name "02. DISTRIBUTOR PART NUMBER") "311-4.70KHRCT-ND")
        (field (name "13. CREATED DATE/NAME") "AUG2018/Hören")
      )
      (libsource (lib "chickenfood") (part "R"))
    )
    (comp (ref "R60")
      (value "4K7")
      (footprint "R0603 Reflow")
      (description "RES SMD 4.7K OHM 1% 1/10W 0603")
      (fields
        (field (name "TOLERANCE") "±1%")
        (field (name "02. DISTRIBUTOR PART NUMBER") "311-4.70KHRCT-ND")
        (field (name "13. CREATED DATE/NAME") "AUG2018/Hören")
      )
      (libsource (lib "chickenfood") (part "R"))
    )
    (comp (ref "R61")
      (value "4K7")
      (footprint "R0603 Reflow")
      (description "RES SMD 4.7K OHM 1% 1/10W 0603")
      (fields
        (field (name "TOLERANCE") "±1%")
        (field (name "02. DISTRIBUTOR PART NUMBER") "311-4.70KHRCT-ND")
        (field (name "13. CREATED DATE/NAME") "AUG2018/Hören")
      )
      (libsource (lib "chickenfood") (part "R"))
    )
    (comp (ref "R62")
      (value "4K7")
      (footprint "R0603 Reflow")
      (description "RES SMD 4.7K OHM 1% 1/10W 0603")
      (fields
        (field (name "TOLERANCE") "±1%")
        (field (name "02. DISTRIBUTOR PART NUMBER") "311-4.70KHRCT-ND")
        (field (name "13. CREATED DATE/NAME") "AUG2018/Hören")
      )
      (libsource (lib "chickenfood") (part "R"))
    )
    (comp (ref "R63")
      (value "4K7")
      (footprint "R0603 Reflow")
      (description "RES SMD 4.7K OHM 1% 1/10W 0603")
      (fields
        (field (name "TOLERANCE") "±1%")
        (field (name "02. DISTRIBUTOR PART NUMBER") "311-4.70KHRCT-ND")
        (field (name "13. CREATED DATE/NAME") "AUG2018/Hören")
      )
      (libsource (lib "chickenfood") (part "R"))
    )
    (comp (ref "R64")
      (value "4K7")
      (footprint "R0603 Reflow")
      (description "RES SMD 4.7K OHM 1% 1/10W 0603")
      (fields
        (field (name "TOLERANCE") "±1%")
        (field (name "02. DISTRIBUTOR PART NUMBER") "311-4.70KHRCT-ND")
        (field (name "13. CREATED DATE/NAME") "AUG2018/Hören")
      )
      (libsource (lib "chickenfood") (part "R"))
    )
    (comp (ref "R65")
      (value "4K7")
      (footprint "R0603 Reflow")
      (description "RES SMD 4.7K OHM 1% 1/10W 0603")
      (fields
        (field (name "TOLERANCE") "±1%")
        (field (name "02. DISTRIBUTOR PART NUMBER") "311-4.70KHRCT-ND")
        (field (name "13. CREATED DATE/NAME") "AUG2018/Hören")
      )
      (libsource (lib "chickenfood") (part "R"))
    )
    (comp (ref "R66")
      (value "4K7")
      (footprint "R0603 Reflow")
      (description "RES SMD 4.7K OHM 1% 1/10W 0603")
      (fields
        (field (name "TOLERANCE") "±1%")
        (field (name "02. DISTRIBUTOR PART NUMBER") "311-4.70KHRCT-ND")
        (field (name "13. CREATED DATE/NAME") "AUG2018/Hören")
      )
      (libsource (lib "chickenfood") (part "R"))
    )
    (comp (ref "R67")
      (value "4K7")
      (footprint "R0603 Reflow")
      (description "RES SMD 4.7K OHM 1% 1/10W 0603")
      (fields
        (field (name "TOLERANCE") "±1%")
        (field (name "02. DISTRIBUTOR PART NUMBER") "311-4.70KHRCT-ND")
        (field (name "13. CREATED DATE/NAME") "AUG2018/Hören")
      )
      (libsource (lib "chickenfood") (part "R"))
    )
    (comp (ref "R68")
      (value "4K7")
      (footprint "R0603 Reflow")
      (description "RES SMD 4.7K OHM 1% 1/10W 0603")
      (fields
        (field (name "TOLERANCE") "±1%")
        (field (name "02. DISTRIBUTOR PART NUMBER") "311-4.70KHRCT-ND")
        (field (name "13. CREATED DATE/NAME") "AUG2018/Hören")
      )
      (libsource (lib "chickenfood") (part "R"))
    )
    (comp (ref "R69")
      (value "4K7")
      (footprint "R0603 Reflow")
      (description "RES SMD 4.7K OHM 1% 1/10W 0603")
      (fields
        (field (name "TOLERANCE") "±1%")
        (field (name "02. DISTRIBUTOR PART NUMBER") "311-4.70KHRCT-ND")
        (field (name "13. CREATED DATE/NAME") "AUG2018/Hören")
      )
      (libsource (lib "chickenfood") (part "R"))
    )
    (comp (ref "R70")
      (value "4K7")
      (footprint "R0603 Reflow")
      (description "RES SMD 4.7K OHM 1% 1/10W 0603")
      (fields
        (field (name "TOLERANCE") "±1%")
        (field (name "02. DISTRIBUTOR PART NUMBER") "311-4.70KHRCT-ND")
        (field (name "13. CREATED DATE/NAME") "AUG2018/Hören")
      )
      (libsource (lib "chickenfood") (part "R"))
    )
    (comp (ref "R71")
      (value "4K7")
      (footprint "R0603 Reflow")
      (description "RES SMD 4.7K OHM 1% 1/10W 0603")
      (fields
        (field (name "TOLERANCE") "±1%")
        (field (name "02. DISTRIBUTOR PART NUMBER") "311-4.70KHRCT-ND")
        (field (name "13. CREATED DATE/NAME") "AUG2018/Hören")
      )
      (libsource (lib "chickenfood") (part "R"))
    )
    (comp (ref "R72")
      (value "4K7")
      (footprint "R0603 Reflow")
      (description "RES SMD 4.7K OHM 1% 1/10W 0603")
      (fields
        (field (name "TOLERANCE") "±1%")
        (field (name "02. DISTRIBUTOR PART NUMBER") "311-4.70KHRCT-ND")
        (field (name "13. CREATED DATE/NAME") "AUG2018/Hören")
      )
      (libsource (lib "chickenfood") (part "R"))
    )
    (comp (ref "R73")
      (value "4K7")
      (footprint "R0603 Reflow")
      (description "RES SMD 4.7K OHM 1% 1/10W 0603")
      (fields
        (field (name "TOLERANCE") "±1%")
        (field (name "02. DISTRIBUTOR PART NUMBER") "311-4.70KHRCT-ND")
        (field (name "13. CREATED DATE/NAME") "AUG2018/Hören")
      )
      (libsource (lib "chickenfood") (part "R"))
    )
    (comp (ref "R74")
      (value "4K7")
      (footprint "R0603 Reflow")
      (description "RES SMD 4.7K OHM 1% 1/10W 0603")
      (fields
        (field (name "TOLERANCE") "±1%")
        (field (name "02. DISTRIBUTOR PART NUMBER") "311-4.70KHRCT-ND")
        (field (name "13. CREATED DATE/NAME") "AUG2018/Hören")
      )
      (libsource (lib "chickenfood") (part "R"))
    )
    (comp (ref "R75")
      (value "4K7")
      (footprint "R0603 Reflow")
      (description "RES SMD 4.7K OHM 1% 1/10W 0603")
      (fields
        (field (name "TOLERANCE") "±1%")
        (field (name "02. DISTRIBUTOR PART NUMBER") "311-4.70KHRCT-ND")
        (field (name "13. CREATED DATE/NAME") "AUG2018/Hören")
      )
      (libsource (lib "chickenfood") (part "R"))
    )
    (comp (ref "R76")
      (value "4K7")
      (footprint "R0603 Reflow")
      (description "RES SMD 4.7K OHM 1% 1/10W 0603")
      (fields
        (field (name "TOLERANCE") "±1%")
        (field (name "02. DISTRIBUTOR PART NUMBER") "311-4.70KHRCT-ND")
        (field (name "13. CREATED DATE/NAME") "AUG2018/Hören")
      )
      (libsource (lib "chickenfood") (part "R"))
    )
    (comp (ref "R77")
      (value "4K7")
      (footprint "R0603 Reflow")
      (description "RES SMD 4.7K OHM 1% 1/10W 0603")
      (fields
        (field (name "TOLERANCE") "±1%")
        (field (name "02. DISTRIBUTOR PART NUMBER") "311-4.70KHRCT-ND")
        (field (name "13. CREATED DATE/NAME") "AUG2018/Hören")
      )
      (libsource (lib "chickenfood") (part "R"))
    )
    (comp (ref "R78")
      (value "4K7")
      (footprint "R0603 Reflow")
      (description "RES SMD 4.7K OHM 1% 1/10W 0603")
      (fields
        (field (name "TOLERANCE") "±1%")
        (field (name "02. DISTRIBUTOR PART NUMBER") "311-4.70KHRCT-ND")
        (field (name "13. CREATED DATE/NAME") "AUG2018/Hören")
      )
      (libsource (lib "chickenfood") (part "R"))
    )
    (comp (ref "R79")
      (value "4K7")
      (footprint "R0603 Reflow")
      (description "RES SMD 4.7K OHM 1% 1/10W 0603")
      (fields
        (field (name "TOLERANCE") "±1%")
        (field (name "02. DISTRIBUTOR PART NUMBER") "311-4.70KHRCT-ND")
        (field (name "13. CREATED DATE/NAME") "AUG2018/Hören")
      )
      (libsource (lib "chickenfood") (part "R"))
    )
    (comp (ref "R80")
      (value "4K7")
      (footprint "R0603 Reflow")
      (description "RES SMD 4.7K OHM 1% 1/10W 0603")
      (fields
        (field (name "TOLERANCE") "±1%")
        (field (name "02. DISTRIBUTOR PART NUMBER") "311-4.70KHRCT-ND")
        (field (name "13. CREATED DATE/NAME") "AUG2018/Hören")
      )
      (libsource (lib "chickenfood") (part "R"))
    )
    (comp (ref "R81")
      (value "4K7")
      (footprint "R0603 Reflow")
      (description "RES SMD 4.7K OHM 1% 1/10W 0603")
      (fields
        (field (name "TOLERANCE") "±1%")
        (field (name "02. DISTRIBUTOR PART NUMBER") "311-4.70KHRCT-ND")
        (field (name "13. CREATED DATE/NAME") "AUG2018/Hören")
      )
      (libsource (lib "chickenfood") (part "R"))
    )
    (comp (ref "R82")
      (value "4K7")
      (footprint "R0603 Reflow")
      (description "RES SMD 4.7K OHM 1% 1/10W 0603")
      (fields
        (field (name "TOLERANCE") "±1%")
        (field (name "02. DISTRIBUTOR PART NUMBER") "311-4.70KHRCT-ND")
        (field (name "13. CREATED DATE/NAME") "AUG2018/Hören")
      )
      (libsource (lib "chickenfood") (part "R"))
    )
    (comp (ref "R83")
      (value "4K7")
      (footprint "R0603 Reflow")
      (description "RES SMD 4.7K OHM 1% 1/10W 0603")
      (fields
        (field (name "TOLERANCE") "±1%")
        (field (name "02. DISTRIBUTOR PART NUMBER") "311-4.70KHRCT-ND")
        (field (name "13. CREATED DATE/NAME") "AUG2018/Hören")
      )
      (libsource (lib "chickenfood") (part "R"))
    )
    (comp (ref "R84")
      (value "4K7")
      (footprint "R0603 Reflow")
      (description "RES SMD 4.7K OHM 1% 1/10W 0603")
      (fields
        (field (name "TOLERANCE") "±1%")
        (field (name "02. DISTRIBUTOR PART NUMBER") "311-4.70KHRCT-ND")
        (field (name "13. CREATED DATE/NAME") "AUG2018/Hören")
      )
      (libsource (lib "chickenfood") (part "R"))
    )
    (comp (ref "R85")
      (value "4K7")
      (footprint "R0603 Reflow")
      (description "RES SMD 4.7K OHM 1% 1/10W 0603")
      (fields
        (field (name "TOLERANCE") "±1%")
        (field (name "02. DISTRIBUTOR PART NUMBER") "311-4.70KHRCT-ND")
        (field (name "13. CREATED DATE/NAME") "AUG2018/Hören")
      )
      (libsource (lib "chickenfood") (part "R"))
    )
    (comp (ref "R86")
      (value "4K7")
      (footprint "R0603 Reflow")
      (description "RES SMD 4.7K OHM 1% 1/10W 0603")
      (fields
        (field (name "TOLERANCE") "±1%")
        (field (name "02. DISTRIBUTOR PART NUMBER") "311-4.70KHRCT-ND")
        (field (name "13. CREATED DATE/NAME") "AUG2018/Hören")
      )
      (libsource (lib "chickenfood") (part "R"))
    )
    (comp (ref "R87")
      (value "4K7")
      (footprint "R0603 Reflow")
      (description "RES SMD 4.7K OHM 1% 1/10W 0603")
      (fields
        (field (name "TOLERANCE") "±1%")
        (field (name "02. DISTRIBUTOR PART NUMBER") "311-4.70KHRCT-ND")
        (field (name "13. CREATED DATE/NAME") "AUG2018/Hören")
      )
      (libsource (lib "chickenfood") (part "R"))
    )
    (comp (ref "R88")
      (value "4K7")
      (footprint "R0603 Reflow")
      (description "RES SMD 4.7K OHM 1% 1/10W 0603")
      (fields
        (field (name "TOLERANCE") "±1%")
        (field (name "02. DISTRIBUTOR PART NUMBER") "311-4.70KHRCT-ND")
        (field (name "13. CREATED DATE/NAME") "AUG2018/Hören")
      )
      (libsource (lib "chickenfood") (part "R"))
    )
    (comp (ref "R89")
      (value "4K7")
      (footprint "R0603 Reflow")
      (description "RES SMD 4.7K OHM 1% 1/10W 0603")
      (fields
        (field (name "TOLERANCE") "±1%")
        (field (name "02. DISTRIBUTOR PART NUMBER") "311-4.70KHRCT-ND")
        (field (name "13. CREATED DATE/NAME") "AUG2018/Hören")
      )
      (libsource (lib "chickenfood") (part "R"))
    )
    (comp (ref "R90")
      (value "4K7")
      (footprint "R0603 Reflow")
      (description "RES SMD 4.7K OHM 1% 1/10W 0603")
      (fields
        (field (name "TOLERANCE") "±1%")
        (field (name "02. DISTRIBUTOR PART NUMBER") "311-4.70KHRCT-ND")
        (field (name "13. CREATED DATE/NAME") "AUG2018/Hören")
      )
      (libsource (lib "chickenfood") (part "R"))
    )
    (comp (ref "R91")
      (value "4K7")
      (footprint "R0603 Reflow")
      (description "RES SMD 4.7K OHM 1% 1/10W 0603")
      (fields
        (field (name "TOLERANCE") "±1%")
        (field (name "02. DISTRIBUTOR PART NUMBER") "311-4.70KHRCT-ND")
        (field (name "13. CREATED DATE/NAME") "AUG2018/Hören")
      )
      (libsource (lib "chickenfood") (part "R"))
    )
    (comp (ref "R92")
      (value "4K7")
      (footprint "R0603 Reflow")
      (description "RES SMD 4.7K OHM 1% 1/10W 0603")
      (fields
        (field (name "TOLERANCE") "±1%")
        (field (name "02. DISTRIBUTOR PART NUMBER") "311-4.70KHRCT-ND")
        (field (name "13. CREATED DATE/NAME") "AUG2018/Hören")
      )
      (libsource (lib "chickenfood") (part "R"))
    )
    (comp (ref "R93")
      (value "4K7")
      (footprint "R0603 Reflow")
      (description "RES SMD 4.7K OHM 1% 1/10W 0603")
      (fields
        (field (name "TOLERANCE") "±1%")
        (field (name "02. DISTRIBUTOR PART NUMBER") "311-4.70KHRCT-ND")
        (field (name "13. CREATED DATE/NAME") "AUG2018/Hören")
      )
      (libsource (lib "chickenfood") (part "R"))
    )
    (comp (ref "R143")
      (value "4K7")
      (footprint "R0603 Reflow")
      (description "RES SMD 4.7K OHM 1% 1/10W 0603")
      (fields
        (field (name "TOLERANCE") "±1%")
        (field (name "02. DISTRIBUTOR PART NUMBER") "311-4.70KHRCT-ND")
        (field (name "13. CREATED DATE/NAME") "AUG2018/Hören")
      )
      (libsource (lib "chickenfood") (part "R"))
    )
    (comp (ref "R144")
      (value "4K7")
      (footprint "R0603 Reflow")
      (description "RES SMD 4.7K OHM 1% 1/10W 0603")
      (fields
        (field (name "TOLERANCE") "±1%")
        (field (name "02. DISTRIBUTOR PART NUMBER") "311-4.70KHRCT-ND")
        (field (name "13. CREATED DATE/NAME") "AUG2018/Hören")
      )
      (libsource (lib "chickenfood") (part "R"))
    )
    (comp (ref "R145")
      (value "4K7")
      (footprint "R0603 Reflow")
      (description "RES SMD 4.7K OHM 1% 1/10W 0603")
      (fields
        (field (name "TOLERANCE") "±1%")
        (field (name "02. DISTRIBUTOR PART NUMBER") "311-4.70KHRCT-ND")
        (field (name "13. CREATED DATE/NAME") "AUG2018/Hören")
      )
      (libsource (lib "chickenfood") (part "R"))
    )
    (comp (ref "R146")
      (value "4K7")
      (footprint "R0603 Reflow")
      (description "RES SMD 4.7K OHM 1% 1/10W 0603")
      (fields
        (field (name "TOLERANCE") "±1%")
        (field (name "02. DISTRIBUTOR PART NUMBER") "311-4.70KHRCT-ND")
        (field (name "13. CREATED DATE/NAME") "AUG2018/Hören")
      )
      (libsource (lib "chickenfood") (part "R"))
    )
    (comp (ref "R147")
      (value "4K7")
      (footprint "R0603 Reflow")
      (description "RES SMD 4.7K OHM 1% 1/10W 0603")
      (fields
        (field (name "TOLERANCE") "±1%")
        (field (name "02. DISTRIBUTOR PART NUMBER") "311-4.70KHRCT-ND")
        (field (name "13. CREATED DATE/NAME") "AUG2018/Hören")
      )
      (libsource (lib "chickenfood") (part "R"))
    )
    (comp (ref "R148")
      (value "4K7")
      (footprint "R0603 Reflow")
      (description "RES SMD 4.7K OHM 1% 1/10W 0603")
      (fields
        (field (name "TOLERANCE") "±1%")
        (field (name "02. DISTRIBUTOR PART NUMBER") "311-4.70KHRCT-ND")
        (field (name "13. CREATED DATE/NAME") "AUG2018/Hören")
      )
      (libsource (lib "chickenfood") (part "R"))
    )
    (comp (ref "R149")
      (value "4K7")
      (footprint "R0603 Reflow")
      (description "RES SMD 4.7K OHM 1% 1/10W 0603")
      (fields
        (field (name "TOLERANCE") "±1%")
        (field (name "02. DISTRIBUTOR PART NUMBER") "311-4.70KHRCT-ND")
        (field (name "13. CREATED DATE/NAME") "AUG2018/Hören")
      )
      (libsource (lib "chickenfood") (part "R"))
    )
    (comp (ref "R150")
      (value "4K7")
      (footprint "R0603 Reflow")
      (description "RES SMD 4.7K OHM 1% 1/10W 0603")
      (fields
        (field (name "TOLERANCE") "±1%")
        (field (name "02. DISTRIBUTOR PART NUMBER") "311-4.70KHRCT-ND")
        (field (name "13. CREATED DATE/NAME") "AUG2018/Hören")
      )
      (libsource (lib "chickenfood") (part "R"))
    )
    (comp (ref "R151")
      (value "4K7")
      (footprint "R0603 Reflow")
      (description "RES SMD 4.7K OHM 1% 1/10W 0603")
      (fields
        (field (name "TOLERANCE") "±1%")
        (field (name "02. DISTRIBUTOR PART NUMBER") "311-4.70KHRCT-ND")
        (field (name "13. CREATED DATE/NAME") "AUG2018/Hören")
      )
      (libsource (lib "chickenfood") (part "R"))
    )
    (comp (ref "R152")
      (value "4K7")
      (footprint "R0603 Reflow")
      (description "RES SMD 4.7K OHM 1% 1/10W 0603")
      (fields
        (field (name "TOLERANCE") "±1%")
        (field (name "02. DISTRIBUTOR PART NUMBER") "311-4.70KHRCT-ND")
        (field (name "13. CREATED DATE/NAME") "AUG2018/Hören")
      )
      (libsource (lib "chickenfood") (part "R"))
    )
    (comp (ref "R153")
      (value "4K7")
      (footprint "R0603 Reflow")
      (description "RES SMD 4.7K OHM 1% 1/10W 0603")
      (fields
        (field (name "TOLERANCE") "±1%")
        (field (name "02. DISTRIBUTOR PART NUMBER") "311-4.70KHRCT-ND")
        (field (name "13. CREATED DATE/NAME") "AUG2018/Hören")
      )
      (libsource (lib "chickenfood") (part "R"))
    )
    (comp (ref "R154")
      (value "4K7")
      (footprint "R0603 Reflow")
      (description "RES SMD 4.7K OHM 1% 1/10W 0603")
      (fields
        (field (name "TOLERANCE") "±1%")
        (field (name "02. DISTRIBUTOR PART NUMBER") "311-4.70KHRCT-ND")
        (field (name "13. CREATED DATE/NAME") "AUG2018/Hören")
      )
      (libsource (lib "chickenfood") (part "R"))
    )
    (comp (ref "R155")
      (value "4K7")
      (footprint "R0603 Reflow")
      (description "RES SMD 4.7K OHM 1% 1/10W 0603")
      (fields
        (field (name "TOLERANCE") "±1%")
        (field (name "02. DISTRIBUTOR PART NUMBER") "311-4.70KHRCT-ND")
        (field (name "13. CREATED DATE/NAME") "AUG2018/Hören")
      )
      (libsource (lib "chickenfood") (part "R"))
    )
    (comp (ref "R156")
      (value "4K7")
      (footprint "R0603 Reflow")
      (description "RES SMD 4.7K OHM 1% 1/10W 0603")
      (fields
        (field (name "TOLERANCE") "±1%")
        (field (name "02. DISTRIBUTOR PART NUMBER") "311-4.70KHRCT-ND")
        (field (name "13. CREATED DATE/NAME") "AUG2018/Hören")
      )
      (libsource (lib "chickenfood") (part "R"))
    )
    (comp (ref "R157")
      (value "4K7")
      (footprint "R0603 Reflow")
      (description "RES SMD 4.7K OHM 1% 1/10W 0603")
      (fields
        (field (name "TOLERANCE") "±1%")
        (field (name "02. DISTRIBUTOR PART NUMBER") "311-4.70KHRCT-ND")
        (field (name "13. CREATED DATE/NAME") "AUG2018/Hören")
      )
      (libsource (lib "chickenfood") (part "R"))
    )
    (comp (ref "R158")
      (value "4K7")
      (footprint "R0603 Reflow")
      (description "RES SMD 4.7K OHM 1% 1/10W 0603")
      (fields
        (field (name "TOLERANCE") "±1%")
        (field (name "02. DISTRIBUTOR PART NUMBER") "311-4.70KHRCT-ND")
        (field (name "13. CREATED DATE/NAME") "AUG2018/Hören")
      )
      (libsource (lib "chickenfood") (part "R"))
    )
    (comp (ref "X28")
      (value "X")
      (footprint "TFC-132-01-F-D-LA")
      (description "CONN HEADER TH RA 48POS 1.27MM")
      (fields
        (field (name "02. DISTRIBUTOR PART NUMBER") "TFC-132-01-F-D-LA")
        (field (name "13. CREATED DATE/NAME") "??? / Hören")
      )
      (libsource (lib "PCB-Tester-Board-V1") (part "TFC-132-01-F-D-LA"))
    )
    (comp (ref "X29")
      (value "X")
      (description "32 x 2 x 1.27mm SOCKET DISCRETE CABL COLORED")
      (fields
        (field (name "02. DISTRIBUTOR PART NUMBER") "SFSD-32-30C-G-15.00-S")
        (field (name "13. CREATED DATE/NAME") "??? / Hören")
      )
      (libsource (lib "PCB-Tester-Board-V1") (part "SFSD-32-30C-G-15.00-S"))
    )
    (comp (ref "X30")
      (value "X")
      (footprint "CONFIG64")
      (description "PCB Tester Configuration Matrix for 64 Relays over 8 ABUSes")
      (fields (field (name "13. CREATED DATE/NAME") "??? / Hören"))
      (libsource (lib "PCB-Tester-Board-V1") (part "CONFIG64"))
    )
  )
  (nets
    (net (code "40") (name "/ABUS0") (class "Default")
      (node (ref "X30") (pin "ABUS0") (pinfunction "ABUS0_ABUS0") (pintype "passive"))
    )
    (net (code "41") (name "/ABUS1") (class "Default")
      (node (ref "X30") (pin "ABUS1") (pinfunction "ABUS1_ABUS1") (pintype "passive"))
    )
    (net (code "42") (name "/ABUS2") (class "Default")
      (node (ref "X30") (pin "ABUS2") (pinfunction "ABUS2_ABUS2") (pintype "passive"))
    )
    (net (code "43") (name "/ABUS3") (class "Default")
      (node (ref "X30") (pin "ABUS3") (pinfunction "ABUS3_ABUS3") (pintype "passive"))
    )
    (net (code "44") (name "/ABUS4") (class "Default")
      (node (ref "X30") (pin "ABUS4") (pinfunction "ABUS4_ABUS4") (pintype "passive"))
    )
    (net (code "45") (name "/ABUS5") (class "Default")
      (node (ref "X30") (pin "ABUS5") (pinfunction "ABUS5_ABUS5") (pintype "passive"))
    )
    (net (code "46") (name "/ABUS6") (class "Default")
      (node (ref "X30") (pin "ABUS6") (pinfunction "ABUS6_ABUS6") (pintype "passive"))
    )
    (net (code "47") (name "/ABUS7") (class "Default")
      (node (ref "X30") (pin "ABUS7") (pinfunction "ABUS7_ABUS7") (pintype "passive"))
    )
    (net (code "49") (name "/DRV40") (class "Default")
      (node (ref "Q28") (pin "1") (pinfunction "G_1") (pintype "passive"))
      (node (ref "R33") (pin "2") (pinfunction "2_2") (pintype "passive"))
    )
    (net (code "50") (name "/DRV41") (class "Default")
      (node (ref "Q31") (pin "1") (pinfunction "G_1") (pintype "passive"))
      (node (ref "R48") (pin "2") (pinfunction "2_2") (pintype "passive"))
    )
    (net (code "51") (name "/DRV42") (class "Default")
      (node (ref "Q32") (pin "1") (pinfunction "G_1") (pintype "passive"))
      (node (ref "R49") (pin "2") (pinfunction "2_2") (pintype "passive"))
    )
    (net (code "52") (name "/DRV43") (class "Default")
      (node (ref "Q33") (pin "1") (pinfunction "G_1") (pintype "passive"))
      (node (ref "R50") (pin "2") (pinfunction "2_2") (pintype "passive"))
    )
    (net (code "53") (name "/DRV44") (class "Default")
      (node (ref "Q34") (pin "1") (pinfunction "G_1") (pintype "passive"))
      (node (ref "R51") (pin "2") (pinfunction "2_2") (pintype "passive"))
    )
    (net (code "54") (name "/DRV45") (class "Default")
      (node (ref "Q35") (pin "1") (pinfunction "G_1") (pintype "passive"))
      (node (ref "R52") (pin "2") (pinfunction "2_2") (pintype "passive"))
    )
    (net (code "55") (name "/DRV46") (class "Default")
      (node (ref "Q36") (pin "1") (pinfunction "G_1") (pintype "passive"))
      (node (ref "R53") (pin "2") (pinfunction "2_2") (pintype "passive"))
    )
    (net (code "56") (name "/DRV47") (class "Default")
      (node (ref "Q37") (pin "1") (pinfunction "G_1") (pintype "passive"))
      (node (ref "R54") (pin "2") (pinfunction "2_2") (pintype "passive"))
    )
    (net (code "57") (name "/DRV48") (class "Default")
      (node (ref "Q38") (pin "1") (pinfunction "G_1") (pintype "passive"))
      (node (ref "R55") (pin "2") (pinfunction "2_2") (pintype "passive"))
    )
    (net (code "58") (name "/DRV49") (class "Default")
      (node (ref "Q39") (pin "1") (pinfunction "G_1") (pintype "passive"))
      (node (ref "R56") (pin "2") (pinfunction "2_2") (pintype "passive"))
    )
    (net (code "59") (name "/DRV50") (class "Default")
      (node (ref "Q40") (pin "1") (pinfunction "G_1") (pintype "passive"))
      (node (ref "R57") (pin "2") (pinfunction "2_2") (pintype "passive"))
    )
    (net (code "60") (name "/DRV51") (class "Default")
      (node (ref "Q41") (pin "1") (pinfunction "G_1") (pintype "passive"))
      (node (ref "R58") (pin "2") (pinfunction "2_2") (pintype "passive"))
    )
    (net (code "61") (name "/DRV52") (class "Default")
      (node (ref "Q42") (pin "1") (pinfunction "G_1") (pintype "passive"))
      (node (ref "R59") (pin "2") (pinfunction "2_2") (pintype "passive"))
    )
    (net (code "62") (name "/DRV53") (class "Default")
      (node (ref "Q43") (pin "1") (pinfunction "G_1") (pintype "passive"))
      (node (ref "R60") (pin "2") (pinfunction "2_2") (pintype "passive"))
    )
    (net (code "63") (name "/DRV54") (class "Default")
      (node (ref "Q44") (pin "1") (pinfunction "G_1") (pintype "passive"))
      (node (ref "R61") (pin "2") (pinfunction "2_2") (pintype "passive"))
    )
    (net (code "64") (name "/DRV55") (class "Default")
      (node (ref "Q45") (pin "1") (pinfunction "G_1") (pintype "passive"))
      (node (ref "R62") (pin "2") (pinfunction "2_2") (pintype "passive"))
    )
    (net (code "65") (name "/DRV56") (class "Default")
      (node (ref "Q27") (pin "1") (pinfunction "G_1") (pintype "passive"))
      (node (ref "R32") (pin "2") (pinfunction "2_2") (pintype "passive"))
    )
    (net (code "66") (name "/DRV57") (class "Default")
      (node (ref "Q46") (pin "1") (pinfunction "G_1") (pintype "passive"))
      (node (ref "R63") (pin "2") (pinfunction "2_2") (pintype "passive"))
    )
    (net (code "67") (name "/DRV58") (class "Default")
      (node (ref "Q47") (pin "1") (pinfunction "G_1") (pintype "passive"))
      (node (ref "R64") (pin "2") (pinfunction "2_2") (pintype "passive"))
    )
    (net (code "68") (name "/DRV59") (class "Default")
      (node (ref "Q48") (pin "1") (pinfunction "G_1") (pintype "passive"))
      (node (ref "R65") (pin "2") (pinfunction "2_2") (pintype "passive"))
    )
    (net (code "69") (name "/DRV60") (class "Default")
      (node (ref "Q49") (pin "1") (pinfunction "G_1") (pintype "passive"))
      (node (ref "R66") (pin "2") (pinfunction "2_2") (pintype "passive"))
    )
    (net (code "70") (name "/DRV61") (class "Default")
      (node (ref "Q50") (pin "1") (pinfunction "G_1") (pintype "passive"))
      (node (ref "R67") (pin "2") (pinfunction "2_2") (pintype "passive"))
    )
    (net (code "71") (name "/DRV62") (class "Default")
      (node (ref "Q51") (pin "1") (pinfunction "G_1") (pintype "passive"))
      (node (ref "R68") (pin "2") (pinfunction "2_2") (pintype "passive"))
    )
    (net (code "72") (name "/DRV63") (class "Default")
      (node (ref "Q52") (pin "1") (pinfunction "G_1") (pintype "passive"))
      (node (ref "R69") (pin "2") (pinfunction "2_2") (pintype "passive"))
    )
    (net (code "73") (name "/DRV64") (class "Default")
      (node (ref "Q53") (pin "1") (pinfunction "G_1") (pintype "passive"))
      (node (ref "R70") (pin "2") (pinfunction "2_2") (pintype "passive"))
    )
    (net (code "74") (name "/DRV65") (class "Default")
      (node (ref "Q54") (pin "1") (pinfunction "G_1") (pintype "passive"))
      (node (ref "R71") (pin "2") (pinfunction "2_2") (pintype "passive"))
    )
    (net (code "75") (name "/DRV66") (class "Default")
      (node (ref "Q55") (pin "1") (pinfunction "G_1") (pintype "passive"))
      (node (ref "R72") (pin "2") (pinfunction "2_2") (pintype "passive"))
    )
    (net (code "76") (name "/DRV67") (class "Default")
      (node (ref "Q56") (pin "1") (pinfunction "G_1") (pintype "passive"))
      (node (ref "R73") (pin "2") (pinfunction "2_2") (pintype "passive"))
    )
    (net (code "77") (name "/DRV68") (class "Default")
      (node (ref "Q57") (pin "1") (pinfunction "G_1") (pintype "passive"))
      (node (ref "R74") (pin "2") (pinfunction "2_2") (pintype "passive"))
    )
    (net (code "78") (name "/DRV69") (class "Default")
      (node (ref "Q58") (pin "1") (pinfunction "G_1") (pintype "passive"))
      (node (ref "R75") (pin "2") (pinfunction "2_2") (pintype "passive"))
    )
    (net (code "79") (name "/DRV70") (class "Default")
      (node (ref "Q59") (pin "1") (pinfunction "G_1") (pintype "passive"))
      (node (ref "R76") (pin "2") (pinfunction "2_2") (pintype "passive"))
    )
    (net (code "80") (name "/DRV71") (class "Default")
      (node (ref "Q60") (pin "1") (pinfunction "G_1") (pintype "passive"))
      (node (ref "R77") (pin "2") (pinfunction "2_2") (pintype "passive"))
    )
    (net (code "81") (name "/DRV72") (class "Default")
      (node (ref "Q61") (pin "1") (pinfunction "G_1") (pintype "passive"))
      (node (ref "R78") (pin "2") (pinfunction "2_2") (pintype "passive"))
    )
    (net (code "82") (name "/DRV73") (class "Default")
      (node (ref "Q62") (pin "1") (pinfunction "G_1") (pintype "passive"))
      (node (ref "R79") (pin "2") (pinfunction "2_2") (pintype "passive"))
    )
    (net (code "83") (name "/DRV74") (class "Default")
      (node (ref "Q63") (pin "1") (pinfunction "G_1") (pintype "passive"))
      (node (ref "R80") (pin "2") (pinfunction "2_2") (pintype "passive"))
    )
    (net (code "84") (name "/DRV75") (class "Default")
      (node (ref "Q64") (pin "1") (pinfunction "G_1") (pintype "passive"))
      (node (ref "R81") (pin "2") (pinfunction "2_2") (pintype "passive"))
    )
    (net (code "85") (name "/DRV76") (class "Default")
      (node (ref "Q65") (pin "1") (pinfunction "G_1") (pintype "passive"))
      (node (ref "R82") (pin "2") (pinfunction "2_2") (pintype "passive"))
    )
    (net (code "86") (name "/DRV77") (class "Default")
      (node (ref "Q66") (pin "1") (pinfunction "G_1") (pintype "passive"))
      (node (ref "R83") (pin "2") (pinfunction "2_2") (pintype "passive"))
    )
    (net (code "87") (name "/DRV78") (class "Default")
      (node (ref "Q67") (pin "1") (pinfunction "G_1") (pintype "passive"))
      (node (ref "R84") (pin "2") (pinfunction "2_2") (pintype "passive"))
    )
    (net (code "88") (name "/DRV79") (class "Default")
      (node (ref "Q68") (pin "1") (pinfunction "G_1") (pintype "passive"))
      (node (ref "R85") (pin "2") (pinfunction "2_2") (pintype "passive"))
    )
    (net (code "89") (name "/DRV80") (class "Default")
      (node (ref "Q69") (pin "1") (pinfunction "G_1") (pintype "passive"))
      (node (ref "R86") (pin "2") (pinfunction "2_2") (pintype "passive"))
    )
    (net (code "90") (name "/DRV81") (class "Default")
      (node (ref "Q70") (pin "1") (pinfunction "G_1") (pintype "passive"))
      (node (ref "R87") (pin "2") (pinfunction "2_2") (pintype "passive"))
    )
    (net (code "91") (name "/DRV82") (class "Default")
      (node (ref "Q71") (pin "1") (pinfunction "G_1") (pintype "passive"))
      (node (ref "R88") (pin "2") (pinfunction "2_2") (pintype "passive"))
    )
    (net (code "92") (name "/DRV83") (class "Default")
      (node (ref "Q72") (pin "1") (pinfunction "G_1") (pintype "passive"))
      (node (ref "R89") (pin "2") (pinfunction "2_2") (pintype "passive"))
    )
    (net (code "93") (name "/DRV84") (class "Default")
      (node (ref "Q73") (pin "1") (pinfunction "G_1") (pintype "passive"))
      (node (ref "R90") (pin "2") (pinfunction "2_2") (pintype "passive"))
    )
    (net (code "94") (name "/DRV85") (class "Default")
      (node (ref "Q74") (pin "1") (pinfunction "G_1") (pintype "passive"))
      (node (ref "R91") (pin "2") (pinfunction "2_2") (pintype "passive"))
    )
    (net (code "95") (name "/DRV86") (class "Default")
      (node (ref "Q75") (pin "1") (pinfunction "G_1") (pintype "passive"))
      (node (ref "R92") (pin "2") (pinfunction "2_2") (pintype "passive"))
    )
    (net (code "96") (name "/DRV87") (class "Default")
      (node (ref "Q76") (pin "1") (pinfunction "G_1") (pintype "passive"))
      (node (ref "R93") (pin "2") (pinfunction "2_2") (pintype "passive"))
    )
    (net (code "97") (name "/DRV88") (class "Default")
      (node (ref "Q81") (pin "1") (pinfunction "G_1") (pintype "passive"))
      (node (ref "R143") (pin "2") (pinfunction "2_2") (pintype "passive"))
    )
    (net (code "98") (name "/DRV89") (class "Default")
      (node (ref "Q82") (pin "1") (pinfunction "G_1") (pintype "passive"))
      (node (ref "R144") (pin "2") (pinfunction "2_2") (pintype "passive"))
    )
    (net (code "99") (name "/DRV90") (class "Default")
      (node (ref "Q83") (pin "1") (pinfunction "G_1") (pintype "passive"))
      (node (ref "R145") (pin "2") (pinfunction "2_2") (pintype "passive"))
    )
    (net (code "100") (name "/DRV91") (class "Default")
      (node (ref "Q84") (pin "1") (pinfunction "G_1") (pintype "passive"))
      (node (ref "R146") (pin "2") (pinfunction "2_2") (pintype "passive"))
    )
    (net (code "101") (name "/DRV92") (class "Default")
      (node (ref "Q85") (pin "1") (pinfunction "G_1") (pintype "passive"))
      (node (ref "R147") (pin "2") (pinfunction "2_2") (pintype "passive"))
    )
    (net (code "102") (name "/DRV93") (class "Default")
      (node (ref "Q86") (pin "1") (pinfunction "G_1") (pintype "passive"))
      (node (ref "R148") (pin "2") (pinfunction "2_2") (pintype "passive"))
    )
    (net (code "103") (name "/DRV94") (class "Default")
      (node (ref "Q87") (pin "1") (pinfunction "G_1") (pintype "passive"))
      (node (ref "R149") (pin "2") (pinfunction "2_2") (pintype "passive"))
    )
    (net (code "104") (name "/DRV95") (class "Default")
      (node (ref "Q88") (pin "1") (pinfunction "G_1") (pintype "passive"))
      (node (ref "R150") (pin "2") (pinfunction "2_2") (pintype "passive"))
    )
    (net (code "105") (name "/DRV96") (class "Default")
      (node (ref "Q89") (pin "1") (pinfunction "G_1") (pintype "passive"))
      (node (ref "R151") (pin "2") (pinfunction "2_2") (pintype "passive"))
    )
    (net (code "106") (name "/DRV97") (class "Default")
      (node (ref "Q90") (pin "1") (pinfunction "G_1") (pintype "passive"))
      (node (ref "R152") (pin "2") (pinfunction "2_2") (pintype "passive"))
    )
    (net (code "107") (name "/DRV98") (class "Default")
      (node (ref "Q91") (pin "1") (pinfunction "G_1") (pintype "passive"))
      (node (ref "R153") (pin "2") (pinfunction "2_2") (pintype "passive"))
    )
    (net (code "108") (name "/DRV99") (class "Default")
      (node (ref "Q92") (pin "1") (pinfunction "G_1") (pintype "passive"))
      (node (ref "R154") (pin "2") (pinfunction "2_2") (pintype "passive"))
    )
    (net (code "109") (name "/DRV100") (class "Default")
      (node (ref "Q93") (pin "1") (pinfunction "G_1") (pintype "passive"))
      (node (ref "R155") (pin "2") (pinfunction "2_2") (pintype "passive"))
    )
    (net (code "110") (name "/DRV101") (class "Default")
      (node (ref "Q94") (pin "1") (pinfunction "G_1") (pintype "passive"))
      (node (ref "R156") (pin "2") (pinfunction "2_2") (pintype "passive"))
    )
    (net (code "111") (name "/DRV102") (class "Default")
      (node (ref "Q95") (pin "1") (pinfunction "G_1") (pintype "passive"))
      (node (ref "R157") (pin "2") (pinfunction "2_2") (pintype "passive"))
    )
    (net (code "112") (name "/DRV103") (class "Default")
      (node (ref "Q96") (pin "1") (pinfunction "G_1") (pintype "passive"))
      (node (ref "R158") (pin "2") (pinfunction "2_2") (pintype "passive"))
    )
    (net (code "114") (name "5V0R") (class "Default")
      (node (ref "K28") (pin "1") (pinfunction "+_1") (pintype "passive"))
      (node (ref "K29") (pin "1") (pinfunction "+_1") (pintype "passive"))
      (node (ref "K30") (pin "1") (pinfunction "+_1") (pintype "passive"))
      (node (ref "K31") (pin "1") (pinfunction "+_1") (pintype "passive"))
      (node (ref "K32") (pin "1") (pinfunction "+_1") (pintype "passive"))
      (node (ref "K33") (pin "1") (pinfunction "+_1") (pintype "passive"))
      (node (ref "K34") (pin "1") (pinfunction "+_1") (pintype "passive"))
      (node (ref "K35") (pin "1") (pinfunction "+_1") (pintype "passive"))
      (node (ref "K36") (pin "1") (pinfunction "+_1") (pintype "passive"))
      (node (ref "K37") (pin "1") (pinfunction "+_1") (pintype "passive"))
      (node (ref "K38") (pin "1") (pinfunction "+_1") (pintype "passive"))
      (node (ref "K39") (pin "1") (pinfunction "+_1") (pintype "passive"))
      (node (ref "K40") (pin "1") (pinfunction "+_1") (pintype "passive"))
      (node (ref "K41") (pin "1") (pinfunction "+_1") (pintype "passive"))
      (node (ref "K42") (pin "1") (pinfunction "+_1") (pintype "passive"))
      (node (ref "K43") (pin "1") (pinfunction "+_1") (pintype "passive"))
      (node (ref "K44") (pin "1") (pinfunction "+_1") (pintype "passive"))
      (node (ref "K45") (pin "1") (pinfunction "+_1") (pintype "passive"))
      (node (ref "K46") (pin "1") (pinfunction "+_1") (pintype "passive"))
      (node (ref "K47") (pin "1") (pinfunction "+_1") (pintype "passive"))
      (node (ref "K48") (pin "1") (pinfunction "+_1") (pintype "passive"))
      (node (ref "K49") (pin "1") (pinfunction "+_1") (pintype "passive"))
      (node (ref "K50") (pin "1") (pinfunction "+_1") (pintype "passive"))
      (node (ref "K51") (pin "1") (pinfunction "+_1") (pintype "passive"))
      (node (ref "K52") (pin "1") (pinfunction "+_1") (pintype "passive"))
      (node (ref "K53") (pin "1") (pinfunction "+_1") (pintype "passive"))
      (node (ref "K54") (pin "1") (pinfunction "+_1") (pintype "passive"))
      (node (ref "K55") (pin "1") (pinfunction "+_1") (pintype "passive"))
      (node (ref "K56") (pin "1") (pinfunction "+_1") (pintype "passive"))
      (node (ref "K57") (pin "1") (pinfunction "+_1") (pintype "passive"))
      (node (ref "K58") (pin "1") (pinfunction "+_1") (pintype "passive"))
      (node (ref "K59") (pin "1") (pinfunction "+_1") (pintype "passive"))
      (node (ref "K60") (pin "1") (pinfunction "+_1") (pintype "passive"))
      (node (ref "K61") (pin "1") (pinfunction "+_1") (pintype "passive"))
      (node (ref "K62") (pin "1") (pinfunction "+_1") (pintype "passive"))
      (node (ref "K63") (pin "1") (pinfunction "+_1") (pintype "passive"))
      (node (ref "K64") (pin "1") (pinfunction "+_1") (pintype "passive"))
      (node (ref "K65") (pin "1") (pinfunction "+_1") (pintype "passive"))
      (node (ref "K66") (pin "1") (pinfunction "+_1") (pintype "passive"))
      (node (ref "K67") (pin "1") (pinfunction "+_1") (pintype "passive"))
      (node (ref "K68") (pin "1") (pinfunction "+_1") (pintype "passive"))
      (node (ref "K69") (pin "1") (pinfunction "+_1") (pintype "passive"))
      (node (ref "K70") (pin "1") (pinfunction "+_1") (pintype "passive"))
      (node (ref "K71") (pin "1") (pinfunction "+_1") (pintype "passive"))
      (node (ref "K72") (pin "1") (pinfunction "+_1") (pintype "passive"))
      (node (ref "K73") (pin "1") (pinfunction "+_1") (pintype "passive"))
      (node (ref "K74") (pin "1") (pinfunction "+_1") (pintype "passive"))
      (node (ref "K75") (pin "1") (pinfunction "+_1") (pintype "passive"))
      (node (ref "K76") (pin "1") (pinfunction "+_1") (pintype "passive"))
      (node (ref "K77") (pin "1") (pinfunction "+_1") (pintype "passive"))
      (node (ref "K78") (pin "1") (pinfunction "+_1") (pintype "passive"))
      (node (ref "K79") (pin "1") (pinfunction "+_1") (pintype "passive"))
      (node (ref "K80") (pin "1") (pinfunction "+_1") (pintype "passive"))
      (node (ref "K81") (pin "1") (pinfunction "+_1") (pintype "passive"))
      (node (ref "K82") (pin "1") (pinfunction "+_1") (pintype "passive"))
      (node (ref "K83") (pin "1") (pinfunction "+_1") (pintype "passive"))
      (node (ref "K84") (pin "1") (pinfunction "+_1") (pintype "passive"))
      (node (ref "K85") (pin "1") (pinfunction "+_1") (pintype "passive"))
      (node (ref "K86") (pin "1") (pinfunction "+_1") (pintype "passive"))
      (node (ref "K87") (pin "1") (pinfunction "+_1") (pintype "passive"))
      (node (ref "K88") (pin "1") (pinfunction "+_1") (pintype "passive"))
      (node (ref "K89") (pin "1") (pinfunction "+_1") (pintype "passive"))
      (node (ref "K90") (pin "1") (pinfunction "+_1") (pintype "passive"))
      (node (ref "K91") (pin "1") (pinfunction "+_1") (pintype "passive"))
    )
    (net (code "115") (name "GND") (class "Default")
      (node (ref "Q27") (pin "2") (pinfunction "S_2") (pintype "passive"))
      (node (ref "Q28") (pin "2") (pinfunction "S_2") (pintype "passive"))
      (node (ref "Q31") (pin "2") (pinfunction "S_2") (pintype "passive"))
      (node (ref "Q32") (pin "2") (pinfunction "S_2") (pintype "passive"))
      (node (ref "Q33") (pin "2") (pinfunction "S_2") (pintype "passive"))
      (node (ref "Q34") (pin "2") (pinfunction "S_2") (pintype "passive"))
      (node (ref "Q35") (pin "2") (pinfunction "S_2") (pintype "passive"))
      (node (ref "Q36") (pin "2") (pinfunction "S_2") (pintype "passive"))
      (node (ref "Q37") (pin "2") (pinfunction "S_2") (pintype "passive"))
      (node (ref "Q38") (pin "2") (pinfunction "S_2") (pintype "passive"))
      (node (ref "Q39") (pin "2") (pinfunction "S_2") (pintype "passive"))
      (node (ref "Q40") (pin "2") (pinfunction "S_2") (pintype "passive"))
      (node (ref "Q41") (pin "2") (pinfunction "S_2") (pintype "passive"))
      (node (ref "Q42") (pin "2") (pinfunction "S_2") (pintype "passive"))
      (node (ref "Q43") (pin "2") (pinfunction "S_2") (pintype "passive"))
      (node (ref "Q44") (pin "2") (pinfunction "S_2") (pintype "passive"))
      (node (ref "Q45") (pin "2") (pinfunction "S_2") (pintype "passive"))
      (node (ref "Q46") (pin "2") (pinfunction "S_2") (pintype "passive"))
      (node (ref "Q47") (pin "2") (pinfunction "S_2") (pintype "passive"))
      (node (ref "Q48") (pin "2") (pinfunction "S_2") (pintype "passive"))
      (node (ref "Q49") (pin "2") (pinfunction "S_2") (pintype "passive"))
      (node (ref "Q50") (pin "2") (pinfunction "S_2") (pintype "passive"))
      (node (ref "Q51") (pin "2") (pinfunction "S_2") (pintype "passive"))
      (node (ref "Q52") (pin "2") (pinfunction "S_2") (pintype "passive"))
      (node (ref "Q53") (pin "2") (pinfunction "S_2") (pintype "passive"))
      (node (ref "Q54") (pin "2") (pinfunction "S_2") (pintype "passive"))
      (node (ref "Q55") (pin "2") (pinfunction "S_2") (pintype "passive"))
      (node (ref "Q56") (pin "2") (pinfunction "S_2") (pintype "passive"))
      (node (ref "Q57") (pin "2") (pinfunction "S_2") (pintype "passive"))
      (node (ref "Q58") (pin "2") (pinfunction "S_2") (pintype "passive"))
      (node (ref "Q59") (pin "2") (pinfunction "S_2") (pintype "passive"))
      (node (ref "Q60") (pin "2") (pinfunction "S_2") (pintype "passive"))
      (node (ref "Q61") (pin "2") (pinfunction "S_2") (pintype "passive"))
      (node (ref "Q62") (pin "2") (pinfunction "S_2") (pintype "passive"))
      (node (ref "Q63") (pin "2") (pinfunction "S_2") (pintype "passive"))
      (node (ref "Q64") (pin "2") (pinfunction "S_2") (pintype "passive"))
      (node (ref "Q65") (pin "2") (pinfunction "S_2") (pintype "passive"))
      (node (ref "Q66") (pin "2") (pinfunction "S_2") (pintype "passive"))
      (node (ref "Q67") (pin "2") (pinfunction "S_2") (pintype "passive"))
      (node (ref "Q68") (pin "2") (pinfunction "S_2") (pintype "passive"))
      (node (ref "Q69") (pin "2") (pinfunction "S_2") (pintype "passive"))
      (node (ref "Q70") (pin "2") (pinfunction "S_2") (pintype "passive"))
      (node (ref "Q71") (pin "2") (pinfunction "S_2") (pintype "passive"))
      (node (ref "Q72") (pin "2") (pinfunction "S_2") (pintype "passive"))
      (node (ref "Q73") (pin "2") (pinfunction "S_2") (pintype "passive"))
      (node (ref "Q74") (pin "2") (pinfunction "S_2") (pintype "passive"))
      (node (ref "Q75") (pin "2") (pinfunction "S_2") (pintype "passive"))
      (node (ref "Q76") (pin "2") (pinfunction "S_2") (pintype "passive"))
      (node (ref "Q81") (pin "2") (pinfunction "S_2") (pintype "passive"))
      (node (ref "Q82") (pin "2") (pinfunction "S_2") (pintype "passive"))
      (node (ref "Q83") (pin "2") (pinfunction "S_2") (pintype "passive"))
      (node (ref "Q84") (pin "2") (pinfunction "S_2") (pintype "passive"))
      (node (ref "Q85") (pin "2") (pinfunction "S_2") (pintype "passive"))
      (node (ref "Q86") (pin "2") (pinfunction "S_2") (pintype "passive"))
      (node (ref "Q87") (pin "2") (pinfunction "S_2") (pintype "passive"))
      (node (ref "Q88") (pin "2") (pinfunction "S_2") (pintype "passive"))
      (node (ref "Q89") (pin "2") (pinfunction "S_2") (pintype "passive"))
      (node (ref "Q90") (pin "2") (pinfunction "S_2") (pintype "passive"))
      (node (ref "Q91") (pin "2") (pinfunction "S_2") (pintype "passive"))
      (node (ref "Q92") (pin "2") (pinfunction "S_2") (pintype "passive"))
      (node (ref "Q93") (pin "2") (pinfunction "S_2") (pintype "passive"))
      (node (ref "Q94") (pin "2") (pinfunction "S_2") (pintype "passive"))
      (node (ref "Q95") (pin "2") (pinfunction "S_2") (pintype "passive"))
      (node (ref "Q96") (pin "2") (pinfunction "S_2") (pintype "passive"))
      (node (ref "R143") (pin "1") (pinfunction "1_1") (pintype "passive"))
      (node (ref "R144") (pin "1") (pinfunction "1_1") (pintype "passive"))
      (node (ref "R145") (pin "1") (pinfunction "1_1") (pintype "passive"))
      (node (ref "R146") (pin "1") (pinfunction "1_1") (pintype "passive"))
      (node (ref "R147") (pin "1") (pinfunction "1_1") (pintype "passive"))
      (node (ref "R148") (pin "1") (pinfunction "1_1") (pintype "passive"))
      (node (ref "R149") (pin "1") (pinfunction "1_1") (pintype "passive"))
      (node (ref "R150") (pin "1") (pinfunction "1_1") (pintype "passive"))
      (node (ref "R151") (pin "1") (pinfunction "1_1") (pintype "passive"))
      (node (ref "R152") (pin "1") (pinfunction "1_1") (pintype "passive"))
      (node (ref "R153") (pin "1") (pinfunction "1_1") (pintype "passive"))
      (node (ref "R154") (pin "1") (pinfunction "1_1") (pintype "passive"))
      (node (ref "R155") (pin "1") (pinfunction "1_1") (pintype "passive"))
      (node (ref "R156") (pin "1") (pinfunction "1_1") (pintype "passive"))
      (node (ref "R157") (pin "1") (pinfunction "1_1") (pintype "passive"))
      (node (ref "R158") (pin "1") (pinfunction "1_1") (pintype "passive"))
      (node (ref "R32") (pin "1") (pinfunction "1_1") (pintype "passive"))
      (node (ref "R33") (pin "1") (pinfunction "1_1") (pintype "passive"))
      (node (ref "R48") (pin "1") (pinfunction "1_1") (pintype "passive"))
      (node (ref "R49") (pin "1") (pinfunction "1_1") (pintype "passive"))
      (node (ref "R50") (pin "1") (pinfunction "1_1") (pintype "passive"))
      (node (ref "R51") (pin "1") (pinfunction "1_1") (pintype "passive"))
      (node (ref "R52") (pin "1") (pinfunction "1_1") (pintype "passive"))
      (node (ref "R53") (pin "1") (pinfunction "1_1") (pintype "passive"))
      (node (ref "R54") (pin "1") (pinfunction "1_1") (pintype "passive"))
      (node (ref "R55") (pin "1") (pinfunction "1_1") (pintype "passive"))
      (node (ref "R56") (pin "1") (pinfunction "1_1") (pintype "passive"))
      (node (ref "R57") (pin "1") (pinfunction "1_1") (pintype "passive"))
      (node (ref "R58") (pin "1") (pinfunction "1_1") (pintype "passive"))
      (node (ref "R59") (pin "1") (pinfunction "1_1") (pintype "passive"))
      (node (ref "R60") (pin "1") (pinfunction "1_1") (pintype "passive"))
      (node (ref "R61") (pin "1") (pinfunction "1_1") (pintype "passive"))
      (node (ref "R62") (pin "1") (pinfunction "1_1") (pintype "passive"))
      (node (ref "R63") (pin "1") (pinfunction "1_1") (pintype "passive"))
      (node (ref "R64") (pin "1") (pinfunction "1_1") (pintype "passive"))
      (node (ref "R65") (pin "1") (pinfunction "1_1") (pintype "passive"))
      (node (ref "R66") (pin "1") (pinfunction "1_1") (pintype "passive"))
      (node (ref "R67") (pin "1") (pinfunction "1_1") (pintype "passive"))
      (node (ref "R68") (pin "1") (pinfunction "1_1") (pintype "passive"))
      (node (ref "R69") (pin "1") (pinfunction "1_1") (pintype "passive"))
      (node (ref "R70") (pin "1") (pinfunction "1_1") (pintype "passive"))
      (node (ref "R71") (pin "1") (pinfunction "1_1") (pintype "passive"))
      (node (ref "R72") (pin "1") (pinfunction "1_1") (pintype "passive"))
      (node (ref "R73") (pin "1") (pinfunction "1_1") (pintype "passive"))
      (node (ref "R74") (pin "1") (pinfunction "1_1") (pintype "passive"))
      (node (ref "R75") (pin "1") (pinfunction "1_1") (pintype "passive"))
      (node (ref "R76") (pin "1") (pinfunction "1_1") (pintype "passive"))
      (node (ref "R77") (pin "1") (pinfunction "1_1") (pintype "passive"))
      (node (ref "R78") (pin "1") (pinfunction "1_1") (pintype "passive"))
      (node (ref "R79") (pin "1") (pinfunction "1_1") (pintype "passive"))
      (node (ref "R80") (pin "1") (pinfunction "1_1") (pintype "passive"))
      (node (ref "R81") (pin "1") (pinfunction "1_1") (pintype "passive"))
      (node (ref "R82") (pin "1") (pinfunction "1_1") (pintype "passive"))
      (node (ref "R83") (pin "1") (pinfunction "1_1") (pintype "passive"))
      (node (ref "R84") (pin "1") (pinfunction "1_1") (pintype "passive"))
      (node (ref "R85") (pin "1") (pinfunction "1_1") (pintype "passive"))
      (node (ref "R86") (pin "1") (pinfunction "1_1") (pintype "passive"))
      (node (ref "R87") (pin "1") (pinfunction "1_1") (pintype "passive"))
      (node (ref "R88") (pin "1") (pinfunction "1_1") (pintype "passive"))
      (node (ref "R89") (pin "1") (pinfunction "1_1") (pintype "passive"))
      (node (ref "R90") (pin "1") (pinfunction "1_1") (pintype "passive"))
      (node (ref "R91") (pin "1") (pinfunction "1_1") (pintype "passive"))
      (node (ref "R92") (pin "1") (pinfunction "1_1") (pintype "passive"))
      (node (ref "R93") (pin "1") (pinfunction "1_1") (pintype "passive"))
    )
    (net (code "116") (name "Net-(K28A-CA)") (class "Default")
      (node (ref "K28") (pin "3") (pinfunction "CA_3") (pintype "passive"))
      (node (ref "X30") (pin "1") (pinfunction "1_1") (pintype "passive"))
    )
    (net (code "117") (name "Net-(K28A-CB)") (class "Default")
      (node (ref "K28") (pin "4") (pinfunction "CB_4") (pintype "passive"))
      (node (ref "X28") (pin "1") (pinfunction "1_1") (pintype "passive"))
    )
    (net (code "118") (name "Net-(K28B--)") (class "Default")
      (node (ref "K28") (pin "2") (pinfunction "-_2") (pintype "passive"))
      (node (ref "Q28") (pin "3") (pinfunction "D_3") (pintype "passive"))
    )
    (net (code "119") (name "Net-(K29A-CA)") (class "Default")
      (node (ref "K29") (pin "3") (pinfunction "CA_3") (pintype "passive"))
      (node (ref "X30") (pin "2") (pinfunction "2_2") (pintype "passive"))
    )
    (net (code "120") (name "Net-(K29A-CB)") (class "Default")
      (node (ref "K29") (pin "4") (pinfunction "CB_4") (pintype "passive"))
      (node (ref "X28") (pin "2") (pinfunction "2_2") (pintype "passive"))
    )
    (net (code "121") (name "Net-(K29B--)") (class "Default")
      (node (ref "K29") (pin "2") (pinfunction "-_2") (pintype "passive"))
      (node (ref "Q31") (pin "3") (pinfunction "D_3") (pintype "passive"))
    )
    (net (code "122") (name "Net-(K30A-CA)") (class "Default")
      (node (ref "K30") (pin "3") (pinfunction "CA_3") (pintype "passive"))
      (node (ref "X30") (pin "3") (pinfunction "3_3") (pintype "passive"))
    )
    (net (code "123") (name "Net-(K30A-CB)") (class "Default")
      (node (ref "K30") (pin "4") (pinfunction "CB_4") (pintype "passive"))
      (node (ref "X28") (pin "3") (pinfunction "3_3") (pintype "passive"))
    )
    (net (code "124") (name "Net-(K30B--)") (class "Default")
      (node (ref "K30") (pin "2") (pinfunction "-_2") (pintype "passive"))
      (node (ref "Q32") (pin "3") (pinfunction "D_3") (pintype "passive"))
    )
    (net (code "125") (name "Net-(K31A-CA)") (class "Default")
      (node (ref "K31") (pin "3") (pinfunction "CA_3") (pintype "passive"))
      (node (ref "X30") (pin "4") (pinfunction "4_4") (pintype "passive"))
    )
    (net (code "126") (name "Net-(K31A-CB)") (class "Default")
      (node (ref "K31") (pin "4") (pinfunction "CB_4") (pintype "passive"))
      (node (ref "X28") (pin "4") (pinfunction "4_4") (pintype "passive"))
    )
    (net (code "127") (name "Net-(K31B--)") (class "Default")
      (node (ref "K31") (pin "2") (pinfunction "-_2") (pintype "passive"))
      (node (ref "Q33") (pin "3") (pinfunction "D_3") (pintype "passive"))
    )
    (net (code "128") (name "Net-(K32A-CA)") (class "Default")
      (node (ref "K32") (pin "3") (pinfunction "CA_3") (pintype "passive"))
      (node (ref "X30") (pin "5") (pinfunction "5_5") (pintype "passive"))
    )
    (net (code "129") (name "Net-(K32A-CB)") (class "Default")
      (node (ref "K32") (pin "4") (pinfunction "CB_4") (pintype "passive"))
      (node (ref "X28") (pin "5") (pinfunction "5_5") (pintype "passive"))
    )
    (net (code "130") (name "Net-(K32B--)") (class "Default")
      (node (ref "K32") (pin "2") (pinfunction "-_2") (pintype "passive"))
      (node (ref "Q34") (pin "3") (pinfunction "D_3") (pintype "passive"))
    )
    (net (code "131") (name "Net-(K33A-CA)") (class "Default")
      (node (ref "K33") (pin "3") (pinfunction "CA_3") (pintype "passive"))
      (node (ref "X30") (pin "6") (pinfunction "6_6") (pintype "passive"))
    )
    (net (code "132") (name "Net-(K33A-CB)") (class "Default")
      (node (ref "K33") (pin "4") (pinfunction "CB_4") (pintype "passive"))
      (node (ref "X28") (pin "6") (pinfunction "6_6") (pintype "passive"))
    )
    (net (code "133") (name "Net-(K33B--)") (class "Default")
      (node (ref "K33") (pin "2") (pinfunction "-_2") (pintype "passive"))
      (node (ref "Q35") (pin "3") (pinfunction "D_3") (pintype "passive"))
    )
    (net (code "134") (name "Net-(K34A-CA)") (class "Default")
      (node (ref "K34") (pin "3") (pinfunction "CA_3") (pintype "passive"))
      (node (ref "X30") (pin "7") (pinfunction "7_7") (pintype "passive"))
    )
    (net (code "135") (name "Net-(K34A-CB)") (class "Default")
      (node (ref "K34") (pin "4") (pinfunction "CB_4") (pintype "passive"))
      (node (ref "X28") (pin "7") (pinfunction "7_7") (pintype "passive"))
    )
    (net (code "136") (name "Net-(K34B--)") (class "Default")
      (node (ref "K34") (pin "2") (pinfunction "-_2") (pintype "passive"))
      (node (ref "Q36") (pin "3") (pinfunction "D_3") (pintype "passive"))
    )
    (net (code "137") (name "Net-(K35A-CA)") (class "Default")
      (node (ref "K35") (pin "3") (pinfunction "CA_3") (pintype "passive"))
      (node (ref "X30") (pin "8") (pinfunction "8_8") (pintype "passive"))
    )
    (net (code "138") (name "Net-(K35A-CB)") (class "Default")
      (node (ref "K35") (pin "4") (pinfunction "CB_4") (pintype "passive"))
      (node (ref "X28") (pin "8") (pinfunction "8_8") (pintype "passive"))
    )
    (net (code "139") (name "Net-(K35B--)") (class "Default")
      (node (ref "K35") (pin "2") (pinfunction "-_2") (pintype "passive"))
      (node (ref "Q37") (pin "3") (pinfunction "D_3") (pintype "passive"))
    )
    (net (code "140") (name "Net-(K36A-CA)") (class "Default")
      (node (ref "K36") (pin "3") (pinfunction "CA_3") (pintype "passive"))
      (node (ref "X30") (pin "9") (pinfunction "9_9") (pintype "passive"))
    )
    (net (code "141") (name "Net-(K36A-CB)") (class "Default")
      (node (ref "K36") (pin "4") (pinfunction "CB_4") (pintype "passive"))
      (node (ref "X28") (pin "9") (pinfunction "9_9") (pintype "passive"))
    )
    (net (code "142") (name "Net-(K36B--)") (class "Default")
      (node (ref "K36") (pin "2") (pinfunction "-_2") (pintype "passive"))
      (node (ref "Q38") (pin "3") (pinfunction "D_3") (pintype "passive"))
    )
    (net (code "143") (name "Net-(K37A-CA)") (class "Default")
      (node (ref "K37") (pin "3") (pinfunction "CA_3") (pintype "passive"))
      (node (ref "X30") (pin "10") (pinfunction "10_10") (pintype "passive"))
    )
    (net (code "144") (name "Net-(K37A-CB)") (class "Default")
      (node (ref "K37") (pin "4") (pinfunction "CB_4") (pintype "passive"))
      (node (ref "X28") (pin "10") (pinfunction "10_10") (pintype "passive"))
    )
    (net (code "145") (name "Net-(K37B--)") (class "Default")
      (node (ref "K37") (pin "2") (pinfunction "-_2") (pintype "passive"))
      (node (ref "Q39") (pin "3") (pinfunction "D_3") (pintype "passive"))
    )
    (net (code "146") (name "Net-(K38A-CA)") (class "Default")
      (node (ref "K38") (pin "3") (pinfunction "CA_3") (pintype "passive"))
      (node (ref "X30") (pin "11") (pinfunction "11_11") (pintype "passive"))
    )
    (net (code "147") (name "Net-(K38A-CB)") (class "Default")
      (node (ref "K38") (pin "4") (pinfunction "CB_4") (pintype "passive"))
      (node (ref "X28") (pin "11") (pinfunction "11_11") (pintype "passive"))
    )
    (net (code "148") (name "Net-(K38B--)") (class "Default")
      (node (ref "K38") (pin "2") (pinfunction "-_2") (pintype "passive"))
      (node (ref "Q40") (pin "3") (pinfunction "D_3") (pintype "passive"))
    )
    (net (code "149") (name "Net-(K39A-CA)") (class "Default")
      (node (ref "K39") (pin "3") (pinfunction "CA_3") (pintype "passive"))
      (node (ref "X30") (pin "12") (pinfunction "12_12") (pintype "passive"))
    )
    (net (code "150") (name "Net-(K39A-CB)") (class "Default")
      (node (ref "K39") (pin "4") (pinfunction "CB_4") (pintype "passive"))
      (node (ref "X28") (pin "12") (pinfunction "12_12") (pintype "passive"))
    )
    (net (code "151") (name "Net-(K39B--)") (class "Default")
      (node (ref "K39") (pin "2") (pinfunction "-_2") (pintype "passive"))
      (node (ref "Q41") (pin "3") (pinfunction "D_3") (pintype "passive"))
    )
    (net (code "152") (name "Net-(K40A-CA)") (class "Default")
      (node (ref "K40") (pin "3") (pinfunction "CA_3") (pintype "passive"))
      (node (ref "X30") (pin "13") (pinfunction "13_13") (pintype "passive"))
    )
    (net (code "153") (name "Net-(K40A-CB)") (class "Default")
      (node (ref "K40") (pin "4") (pinfunction "CB_4") (pintype "passive"))
      (node (ref "X28") (pin "13") (pinfunction "13_13") (pintype "passive"))
    )
    (net (code "154") (name "Net-(K40B--)") (class "Default")
      (node (ref "K40") (pin "2") (pinfunction "-_2") (pintype "passive"))
      (node (ref "Q42") (pin "3") (pinfunction "D_3") (pintype "passive"))
    )
    (net (code "155") (name "Net-(K41A-CA)") (class "Default")
      (node (ref "K41") (pin "3") (pinfunction "CA_3") (pintype "passive"))
      (node (ref "X30") (pin "14") (pinfunction "14_14") (pintype "passive"))
    )
    (net (code "156") (name "Net-(K41A-CB)") (class "Default")
      (node (ref "K41") (pin "4") (pinfunction "CB_4") (pintype "passive"))
      (node (ref "X28") (pin "14") (pinfunction "14_14") (pintype "passive"))
    )
    (net (code "157") (name "Net-(K41B--)") (class "Default")
      (node (ref "K41") (pin "2") (pinfunction "-_2") (pintype "passive"))
      (node (ref "Q43") (pin "3") (pinfunction "D_3") (pintype "passive"))
    )
    (net (code "158") (name "Net-(K42A-CA)") (class "Default")
      (node (ref "K42") (pin "3") (pinfunction "CA_3") (pintype "passive"))
      (node (ref "X30") (pin "15") (pinfunction "15_15") (pintype "passive"))
    )
    (net (code "159") (name "Net-(K42A-CB)") (class "Default")
      (node (ref "K42") (pin "4") (pinfunction "CB_4") (pintype "passive"))
      (node (ref "X28") (pin "15") (pinfunction "15_15") (pintype "passive"))
    )
    (net (code "160") (name "Net-(K42B--)") (class "Default")
      (node (ref "K42") (pin "2") (pinfunction "-_2") (pintype "passive"))
      (node (ref "Q44") (pin "3") (pinfunction "D_3") (pintype "passive"))
    )
    (net (code "161") (name "Net-(K43A-CA)") (class "Default")
      (node (ref "K43") (pin "3") (pinfunction "CA_3") (pintype "passive"))
      (node (ref "X30") (pin "16") (pinfunction "16_16") (pintype "passive"))
    )
    (net (code "162") (name "Net-(K43A-CB)") (class "Default")
      (node (ref "K43") (pin "4") (pinfunction "CB_4") (pintype "passive"))
      (node (ref "X28") (pin "16") (pinfunction "16_16") (pintype "passive"))
    )
    (net (code "163") (name "Net-(K43B--)") (class "Default")
      (node (ref "K43") (pin "2") (pinfunction "-_2") (pintype "passive"))
      (node (ref "Q45") (pin "3") (pinfunction "D_3") (pintype "passive"))
    )
    (net (code "164") (name "Net-(K44A-CA)") (class "Default")
      (node (ref "K44") (pin "3") (pinfunction "CA_3") (pintype "passive"))
      (node (ref "X30") (pin "17") (pinfunction "17_17") (pintype "passive"))
    )
    (net (code "165") (name "Net-(K44A-CB)") (class "Default")
      (node (ref "K44") (pin "4") (pinfunction "CB_4") (pintype "passive"))
      (node (ref "X28") (pin "17") (pinfunction "17_17") (pintype "passive"))
    )
    (net (code "166") (name "Net-(K44B--)") (class "Default")
      (node (ref "K44") (pin "2") (pinfunction "-_2") (pintype "passive"))
      (node (ref "Q27") (pin "3") (pinfunction "D_3") (pintype "passive"))
    )
    (net (code "167") (name "Net-(K45A-CA)") (class "Default")
      (node (ref "K45") (pin "3") (pinfunction "CA_3") (pintype "passive"))
      (node (ref "X30") (pin "18") (pinfunction "18_18") (pintype "passive"))
    )
    (net (code "168") (name "Net-(K45A-CB)") (class "Default")
      (node (ref "K45") (pin "4") (pinfunction "CB_4") (pintype "passive"))
      (node (ref "X28") (pin "18") (pinfunction "18_18") (pintype "passive"))
    )
    (net (code "169") (name "Net-(K45B--)") (class "Default")
      (node (ref "K45") (pin "2") (pinfunction "-_2") (pintype "passive"))
      (node (ref "Q46") (pin "3") (pinfunction "D_3") (pintype "passive"))
    )
    (net (code "170") (name "Net-(K46A-CA)") (class "Default")
      (node (ref "K46") (pin "3") (pinfunction "CA_3") (pintype "passive"))
      (node (ref "X30") (pin "19") (pinfunction "19_19") (pintype "passive"))
    )
    (net (code "171") (name "Net-(K46A-CB)") (class "Default")
      (node (ref "K46") (pin "4") (pinfunction "CB_4") (pintype "passive"))
      (node (ref "X28") (pin "19") (pinfunction "19_19") (pintype "passive"))
    )
    (net (code "172") (name "Net-(K46B--)") (class "Default")
      (node (ref "K46") (pin "2") (pinfunction "-_2") (pintype "passive"))
      (node (ref "Q47") (pin "3") (pinfunction "D_3") (pintype "passive"))
    )
    (net (code "173") (name "Net-(K47A-CA)") (class "Default")
      (node (ref "K47") (pin "3") (pinfunction "CA_3") (pintype "passive"))
      (node (ref "X30") (pin "20") (pinfunction "20_20") (pintype "passive"))
    )
    (net (code "174") (name "Net-(K47A-CB)") (class "Default")
      (node (ref "K47") (pin "4") (pinfunction "CB_4") (pintype "passive"))
      (node (ref "X28") (pin "20") (pinfunction "20_20") (pintype "passive"))
    )
    (net (code "175") (name "Net-(K47B--)") (class "Default")
      (node (ref "K47") (pin "2") (pinfunction "-_2") (pintype "passive"))
      (node (ref "Q48") (pin "3") (pinfunction "D_3") (pintype "passive"))
    )
    (net (code "176") (name "Net-(K48A-CA)") (class "Default")
      (node (ref "K48") (pin "3") (pinfunction "CA_3") (pintype "passive"))
      (node (ref "X30") (pin "21") (pinfunction "21_21") (pintype "passive"))
    )
    (net (code "177") (name "Net-(K48A-CB)") (class "Default")
      (node (ref "K48") (pin "4") (pinfunction "CB_4") (pintype "passive"))
      (node (ref "X28") (pin "21") (pinfunction "21_21") (pintype "passive"))
    )
    (net (code "178") (name "Net-(K48B--)") (class "Default")
      (node (ref "K48") (pin "2") (pinfunction "-_2") (pintype "passive"))
      (node (ref "Q49") (pin "3") (pinfunction "D_3") (pintype "passive"))
    )
    (net (code "179") (name "Net-(K49A-CA)") (class "Default")
      (node (ref "K49") (pin "3") (pinfunction "CA_3") (pintype "passive"))
      (node (ref "X30") (pin "22") (pinfunction "22_22") (pintype "passive"))
    )
    (net (code "180") (name "Net-(K49A-CB)") (class "Default")
      (node (ref "K49") (pin "4") (pinfunction "CB_4") (pintype "passive"))
      (node (ref "X28") (pin "22") (pinfunction "22_22") (pintype "passive"))
    )
    (net (code "181") (name "Net-(K49B--)") (class "Default")
      (node (ref "K49") (pin "2") (pinfunction "-_2") (pintype "passive"))
      (node (ref "Q50") (pin "3") (pinfunction "D_3") (pintype "passive"))
    )
    (net (code "182") (name "Net-(K50A-CA)") (class "Default")
      (node (ref "K50") (pin "3") (pinfunction "CA_3") (pintype "passive"))
      (node (ref "X30") (pin "23") (pinfunction "23_23") (pintype "passive"))
    )
    (net (code "183") (name "Net-(K50A-CB)") (class "Default")
      (node (ref "K50") (pin "4") (pinfunction "CB_4") (pintype "passive"))
      (node (ref "X28") (pin "23") (pinfunction "23_23") (pintype "passive"))
    )
    (net (code "184") (name "Net-(K50B--)") (class "Default")
      (node (ref "K50") (pin "2") (pinfunction "-_2") (pintype "passive"))
      (node (ref "Q51") (pin "3") (pinfunction "D_3") (pintype "passive"))
    )
    (net (code "185") (name "Net-(K51A-CA)") (class "Default")
      (node (ref "K51") (pin "3") (pinfunction "CA_3") (pintype "passive"))
      (node (ref "X30") (pin "24") (pinfunction "24_24") (pintype "passive"))
    )
    (net (code "186") (name "Net-(K51A-CB)") (class "Default")
      (node (ref "K51") (pin "4") (pinfunction "CB_4") (pintype "passive"))
      (node (ref "X28") (pin "24") (pinfunction "24_24") (pintype "passive"))
    )
    (net (code "187") (name "Net-(K51B--)") (class "Default")
      (node (ref "K51") (pin "2") (pinfunction "-_2") (pintype "passive"))
      (node (ref "Q52") (pin "3") (pinfunction "D_3") (pintype "passive"))
    )
    (net (code "188") (name "Net-(K52A-CA)") (class "Default")
      (node (ref "K52") (pin "3") (pinfunction "CA_3") (pintype "passive"))
      (node (ref "X30") (pin "25") (pinfunction "25_25") (pintype "passive"))
    )
    (net (code "189") (name "Net-(K52A-CB)") (class "Default")
      (node (ref "K52") (pin "4") (pinfunction "CB_4") (pintype "passive"))
      (node (ref "X28") (pin "25") (pinfunction "25_25") (pintype "passive"))
    )
    (net (code "190") (name "Net-(K52B--)") (class "Default")
      (node (ref "K52") (pin "2") (pinfunction "-_2") (pintype "passive"))
      (node (ref "Q53") (pin "3") (pinfunction "D_3") (pintype "passive"))
    )
    (net (code "191") (name "Net-(K53A-CA)") (class "Default")
      (node (ref "K53") (pin "3") (pinfunction "CA_3") (pintype "passive"))
      (node (ref "X30") (pin "26") (pinfunction "26_26") (pintype "passive"))
    )
    (net (code "192") (name "Net-(K53A-CB)") (class "Default")
      (node (ref "K53") (pin "4") (pinfunction "CB_4") (pintype "passive"))
      (node (ref "X28") (pin "26") (pinfunction "26_26") (pintype "passive"))
    )
    (net (code "193") (name "Net-(K53B--)") (class "Default")
      (node (ref "K53") (pin "2") (pinfunction "-_2") (pintype "passive"))
      (node (ref "Q54") (pin "3") (pinfunction "D_3") (pintype "passive"))
    )
    (net (code "194") (name "Net-(K54A-CA)") (class "Default")
      (node (ref "K54") (pin "3") (pinfunction "CA_3") (pintype "passive"))
      (node (ref "X30") (pin "27") (pinfunction "27_27") (pintype "passive"))
    )
    (net (code "195") (name "Net-(K54A-CB)") (class "Default")
      (node (ref "K54") (pin "4") (pinfunction "CB_4") (pintype "passive"))
      (node (ref "X28") (pin "27") (pinfunction "27_27") (pintype "passive"))
    )
    (net (code "196") (name "Net-(K54B--)") (class "Default")
      (node (ref "K54") (pin "2") (pinfunction "-_2") (pintype "passive"))
      (node (ref "Q55") (pin "3") (pinfunction "D_3") (pintype "passive"))
    )
    (net (code "197") (name "Net-(K55A-CA)") (class "Default")
      (node (ref "K55") (pin "3") (pinfunction "CA_3") (pintype "passive"))
      (node (ref "X30") (pin "28") (pinfunction "28_28") (pintype "passive"))
    )
    (net (code "198") (name "Net-(K55A-CB)") (class "Default")
      (node (ref "K55") (pin "4") (pinfunction "CB_4") (pintype "passive"))
      (node (ref "X28") (pin "28") (pinfunction "28_28") (pintype "passive"))
    )
    (net (code "199") (name "Net-(K55B--)") (class "Default")
      (node (ref "K55") (pin "2") (pinfunction "-_2") (pintype "passive"))
      (node (ref "Q56") (pin "3") (pinfunction "D_3") (pintype "passive"))
    )
    (net (code "200") (name "Net-(K56A-CA)") (class "Default")
      (node (ref "K56") (pin "3") (pinfunction "CA_3") (pintype "passive"))
      (node (ref "X30") (pin "29") (pinfunction "29_29") (pintype "passive"))
    )
    (net (code "201") (name "Net-(K56A-CB)") (class "Default")
      (node (ref "K56") (pin "4") (pinfunction "CB_4") (pintype "passive"))
      (node (ref "X28") (pin "29") (pinfunction "29_29") (pintype "passive"))
    )
    (net (code "202") (name "Net-(K56B--)") (class "Default")
      (node (ref "K56") (pin "2") (pinfunction "-_2") (pintype "passive"))
      (node (ref "Q57") (pin "3") (pinfunction "D_3") (pintype "passive"))
    )
    (net (code "203") (name "Net-(K57A-CA)") (class "Default")
      (node (ref "K57") (pin "3") (pinfunction "CA_3") (pintype "passive"))
      (node (ref "X30") (pin "30") (pinfunction "30_30") (pintype "passive"))
    )
    (net (code "204") (name "Net-(K57A-CB)") (class "Default")
      (node (ref "K57") (pin "4") (pinfunction "CB_4") (pintype "passive"))
      (node (ref "X28") (pin "30") (pinfunction "30_30") (pintype "passive"))
    )
    (net (code "205") (name "Net-(K57B--)") (class "Default")
      (node (ref "K57") (pin "2") (pinfunction "-_2") (pintype "passive"))
      (node (ref "Q58") (pin "3") (pinfunction "D_3") (pintype "passive"))
    )
    (net (code "206") (name "Net-(K58A-CA)") (class "Default")
      (node (ref "K58") (pin "3") (pinfunction "CA_3") (pintype "passive"))
      (node (ref "X30") (pin "31") (pinfunction "31_31") (pintype "passive"))
    )
    (net (code "207") (name "Net-(K58A-CB)") (class "Default")
      (node (ref "K58") (pin "4") (pinfunction "CB_4") (pintype "passive"))
      (node (ref "X28") (pin "31") (pinfunction "31_31") (pintype "passive"))
    )
    (net (code "208") (name "Net-(K58B--)") (class "Default")
      (node (ref "K58") (pin "2") (pinfunction "-_2") (pintype "passive"))
      (node (ref "Q59") (pin "3") (pinfunction "D_3") (pintype "passive"))
    )
    (net (code "209") (name "Net-(K59A-CA)") (class "Default")
      (node (ref "K59") (pin "3") (pinfunction "CA_3") (pintype "passive"))
      (node (ref "X30") (pin "32") (pinfunction "32_32") (pintype "passive"))
    )
    (net (code "210") (name "Net-(K59A-CB)") (class "Default")
      (node (ref "K59") (pin "4") (pinfunction "CB_4") (pintype "passive"))
      (node (ref "X28") (pin "32") (pinfunction "32_32") (pintype "passive"))
    )
    (net (code "211") (name "Net-(K59B--)") (class "Default")
      (node (ref "K59") (pin "2") (pinfunction "-_2") (pintype "passive"))
      (node (ref "Q60") (pin "3") (pinfunction "D_3") (pintype "passive"))
    )
    (net (code "212") (name "Net-(K60A-CA)") (class "Default")
      (node (ref "K60") (pin "3") (pinfunction "CA_3") (pintype "passive"))
      (node (ref "X30") (pin "33") (pinfunction "33_33") (pintype "passive"))
    )
    (net (code "213") (name "Net-(K60A-CB)") (class "Default")
      (node (ref "K60") (pin "4") (pinfunction "CB_4") (pintype "passive"))
      (node (ref "X28") (pin "33") (pinfunction "33_33") (pintype "passive"))
    )
    (net (code "214") (name "Net-(K60B--)") (class "Default")
      (node (ref "K60") (pin "2") (pinfunction "-_2") (pintype "passive"))
      (node (ref "Q61") (pin "3") (pinfunction "D_3") (pintype "passive"))
    )
    (net (code "215") (name "Net-(K61A-CA)") (class "Default")
      (node (ref "K61") (pin "3") (pinfunction "CA_3") (pintype "passive"))
      (node (ref "X30") (pin "34") (pinfunction "34_34") (pintype "passive"))
    )
    (net (code "216") (name "Net-(K61A-CB)") (class "Default")
      (node (ref "K61") (pin "4") (pinfunction "CB_4") (pintype "passive"))
      (node (ref "X28") (pin "34") (pinfunction "34_34") (pintype "passive"))
    )
    (net (code "217") (name "Net-(K61B--)") (class "Default")
      (node (ref "K61") (pin "2") (pinfunction "-_2") (pintype "passive"))
      (node (ref "Q62") (pin "3") (pinfunction "D_3") (pintype "passive"))
    )
    (net (code "218") (name "Net-(K62A-CA)") (class "Default")
      (node (ref "K62") (pin "3") (pinfunction "CA_3") (pintype "passive"))
      (node (ref "X30") (pin "35") (pinfunction "35_35") (pintype "passive"))
    )
    (net (code "219") (name "Net-(K62A-CB)") (class "Default")
      (node (ref "K62") (pin "4") (pinfunction "CB_4") (pintype "passive"))
      (node (ref "X28") (pin "35") (pinfunction "35_35") (pintype "passive"))
    )
    (net (code "220") (name "Net-(K62B--)") (class "Default")
      (node (ref "K62") (pin "2") (pinfunction "-_2") (pintype "passive"))
      (node (ref "Q63") (pin "3") (pinfunction "D_3") (pintype "passive"))
    )
    (net (code "221") (name "Net-(K63A-CA)") (class "Default")
      (node (ref "K63") (pin "3") (pinfunction "CA_3") (pintype "passive"))
      (node (ref "X30") (pin "36") (pinfunction "36_36") (pintype "passive"))
    )
    (net (code "222") (name "Net-(K63A-CB)") (class "Default")
      (node (ref "K63") (pin "4") (pinfunction "CB_4") (pintype "passive"))
      (node (ref "X28") (pin "36") (pinfunction "36_36") (pintype "passive"))
    )
    (net (code "223") (name "Net-(K63B--)") (class "Default")
      (node (ref "K63") (pin "2") (pinfunction "-_2") (pintype "passive"))
      (node (ref "Q64") (pin "3") (pinfunction "D_3") (pintype "passive"))
    )
    (net (code "224") (name "Net-(K64A-CA)") (class "Default")
      (node (ref "K64") (pin "3") (pinfunction "CA_3") (pintype "passive"))
      (node (ref "X30") (pin "37") (pinfunction "37_37") (pintype "passive"))
    )
    (net (code "225") (name "Net-(K64A-CB)") (class "Default")
      (node (ref "K64") (pin "4") (pinfunction "CB_4") (pintype "passive"))
      (node (ref "X28") (pin "37") (pinfunction "37_37") (pintype "passive"))
    )
    (net (code "226") (name "Net-(K64B--)") (class "Default")
      (node (ref "K64") (pin "2") (pinfunction "-_2") (pintype "passive"))
      (node (ref "Q65") (pin "3") (pinfunction "D_3") (pintype "passive"))
    )
    (net (code "227") (name "Net-(K65A-CA)") (class "Default")
      (node (ref "K65") (pin "3") (pinfunction "CA_3") (pintype "passive"))
      (node (ref "X30") (pin "38") (pinfunction "38_38") (pintype "passive"))
    )
    (net (code "228") (name "Net-(K65A-CB)") (class "Default")
      (node (ref "K65") (pin "4") (pinfunction "CB_4") (pintype "passive"))
      (node (ref "X28") (pin "38") (pinfunction "38_38") (pintype "passive"))
    )
    (net (code "229") (name "Net-(K65B--)") (class "Default")
      (node (ref "K65") (pin "2") (pinfunction "-_2") (pintype "passive"))
      (node (ref "Q66") (pin "3") (pinfunction "D_3") (pintype "passive"))
    )
    (net (code "230") (name "Net-(K66A-CA)") (class "Default")
      (node (ref "K66") (pin "3") (pinfunction "CA_3") (pintype "passive"))
      (node (ref "X30") (pin "39") (pinfunction "39_39") (pintype "passive"))
    )
    (net (code "231") (name "Net-(K66A-CB)") (class "Default")
      (node (ref "K66") (pin "4") (pinfunction "CB_4") (pintype "passive"))
      (node (ref "X28") (pin "39") (pinfunction "39_39") (pintype "passive"))
    )
    (net (code "232") (name "Net-(K66B--)") (class "Default")
      (node (ref "K66") (pin "2") (pinfunction "-_2") (pintype "passive"))
      (node (ref "Q67") (pin "3") (pinfunction "D_3") (pintype "passive"))
    )
    (net (code "233") (name "Net-(K67A-CA)") (class "Default")
      (node (ref "K67") (pin "3") (pinfunction "CA_3") (pintype "passive"))
      (node (ref "X30") (pin "40") (pinfunction "40_40") (pintype "passive"))
    )
    (net (code "234") (name "Net-(K67A-CB)") (class "Default")
      (node (ref "K67") (pin "4") (pinfunction "CB_4") (pintype "passive"))
      (node (ref "X28") (pin "40") (pinfunction "40_40") (pintype "passive"))
    )
    (net (code "235") (name "Net-(K67B--)") (class "Default")
      (node (ref "K67") (pin "2") (pinfunction "-_2") (pintype "passive"))
      (node (ref "Q68") (pin "3") (pinfunction "D_3") (pintype "passive"))
    )
    (net (code "236") (name "Net-(K68A-CA)") (class "Default")
      (node (ref "K68") (pin "3") (pinfunction "CA_3") (pintype "passive"))
      (node (ref "X30") (pin "41") (pinfunction "41_41") (pintype "passive"))
    )
    (net (code "237") (name "Net-(K68A-CB)") (class "Default")
      (node (ref "K68") (pin "4") (pinfunction "CB_4") (pintype "passive"))
      (node (ref "X28") (pin "41") (pinfunction "41_41") (pintype "passive"))
    )
    (net (code "238") (name "Net-(K68B--)") (class "Default")
      (node (ref "K68") (pin "2") (pinfunction "-_2") (pintype "passive"))
      (node (ref "Q69") (pin "3") (pinfunction "D_3") (pintype "passive"))
    )
    (net (code "239") (name "Net-(K69A-CA)") (class "Default")
      (node (ref "K69") (pin "3") (pinfunction "CA_3") (pintype "passive"))
      (node (ref "X30") (pin "42") (pinfunction "42_42") (pintype "passive"))
    )
    (net (code "240") (name "Net-(K69A-CB)") (class "Default")
      (node (ref "K69") (pin "4") (pinfunction "CB_4") (pintype "passive"))
      (node (ref "X28") (pin "42") (pinfunction "42_42") (pintype "passive"))
    )
    (net (code "241") (name "Net-(K69B--)") (class "Default")
      (node (ref "K69") (pin "2") (pinfunction "-_2") (pintype "passive"))
      (node (ref "Q70") (pin "3") (pinfunction "D_3") (pintype "passive"))
    )
    (net (code "242") (name "Net-(K70A-CA)") (class "Default")
      (node (ref "K70") (pin "3") (pinfunction "CA_3") (pintype "passive"))
      (node (ref "X30") (pin "43") (pinfunction "43_43") (pintype "passive"))
    )
    (net (code "243") (name "Net-(K70A-CB)") (class "Default")
      (node (ref "K70") (pin "4") (pinfunction "CB_4") (pintype "passive"))
      (node (ref "X28") (pin "43") (pinfunction "43_43") (pintype "passive"))
    )
    (net (code "244") (name "Net-(K70B--)") (class "Default")
      (node (ref "K70") (pin "2") (pinfunction "-_2") (pintype "passive"))
      (node (ref "Q71") (pin "3") (pinfunction "D_3") (pintype "passive"))
    )
    (net (code "245") (name "Net-(K71A-CA)") (class "Default")
      (node (ref "K71") (pin "3") (pinfunction "CA_3") (pintype "passive"))
      (node (ref "X30") (pin "44") (pinfunction "44_44") (pintype "passive"))
    )
    (net (code "246") (name "Net-(K71A-CB)") (class "Default")
      (node (ref "K71") (pin "4") (pinfunction "CB_4") (pintype "passive"))
      (node (ref "X28") (pin "44") (pinfunction "44_44") (pintype "passive"))
    )
    (net (code "247") (name "Net-(K71B--)") (class "Default")
      (node (ref "K71") (pin "2") (pinfunction "-_2") (pintype "passive"))
      (node (ref "Q72") (pin "3") (pinfunction "D_3") (pintype "passive"))
    )
    (net (code "248") (name "Net-(K72A-CA)") (class "Default")
      (node (ref "K72") (pin "3") (pinfunction "CA_3") (pintype "passive"))
      (node (ref "X30") (pin "45") (pinfunction "45_45") (pintype "passive"))
    )
    (net (code "249") (name "Net-(K72A-CB)") (class "Default")
      (node (ref "K72") (pin "4") (pinfunction "CB_4") (pintype "passive"))
      (node (ref "X28") (pin "45") (pinfunction "45_45") (pintype "passive"))
    )
    (net (code "250") (name "Net-(K72B--)") (class "Default")
      (node (ref "K72") (pin "2") (pinfunction "-_2") (pintype "passive"))
      (node (ref "Q73") (pin "3") (pinfunction "D_3") (pintype "passive"))
    )
    (net (code "251") (name "Net-(K73A-CA)") (class "Default")
      (node (ref "K73") (pin "3") (pinfunction "CA_3") (pintype "passive"))
      (node (ref "X30") (pin "46") (pinfunction "46_46") (pintype "passive"))
    )
    (net (code "252") (name "Net-(K73A-CB)") (class "Default")
      (node (ref "K73") (pin "4") (pinfunction "CB_4") (pintype "passive"))
      (node (ref "X28") (pin "46") (pinfunction "46_46") (pintype "passive"))
    )
    (net (code "253") (name "Net-(K73B--)") (class "Default")
      (node (ref "K73") (pin "2") (pinfunction "-_2") (pintype "passive"))
      (node (ref "Q74") (pin "3") (pinfunction "D_3") (pintype "passive"))
    )
    (net (code "254") (name "Net-(K74A-CA)") (class "Default")
      (node (ref "K74") (pin "3") (pinfunction "CA_3") (pintype "passive"))
      (node (ref "X30") (pin "47") (pinfunction "47_47") (pintype "passive"))
    )
    (net (code "255") (name "Net-(K74A-CB)") (class "Default")
      (node (ref "K74") (pin "4") (pinfunction "CB_4") (pintype "passive"))
      (node (ref "X28") (pin "47") (pinfunction "47_47") (pintype "passive"))
    )
    (net (code "256") (name "Net-(K74B--)") (class "Default")
      (node (ref "K74") (pin "2") (pinfunction "-_2") (pintype "passive"))
      (node (ref "Q75") (pin "3") (pinfunction "D_3") (pintype "passive"))
    )
    (net (code "257") (name "Net-(K75A-CA)") (class "Default")
      (node (ref "K75") (pin "3") (pinfunction "CA_3") (pintype "passive"))
      (node (ref "X30") (pin "48") (pinfunction "48_48") (pintype "passive"))
    )
    (net (code "258") (name "Net-(K75A-CB)") (class "Default")
      (node (ref "K75") (pin "4") (pinfunction "CB_4") (pintype "passive"))
      (node (ref "X28") (pin "48") (pinfunction "48_48") (pintype "passive"))
    )
    (net (code "259") (name "Net-(K75B--)") (class "Default")
      (node (ref "K75") (pin "2") (pinfunction "-_2") (pintype "passive"))
      (node (ref "Q76") (pin "3") (pinfunction "D_3") (pintype "passive"))
    )
    (net (code "260") (name "Net-(K76A-CA)") (class "Default")
      (node (ref "K76") (pin "3") (pinfunction "CA_3") (pintype "passive"))
      (node (ref "X30") (pin "49") (pinfunction "49_49") (pintype "passive"))
    )
    (net (code "261") (name "Net-(K76A-CB)") (class "Default")
      (node (ref "K76") (pin "4") (pinfunction "CB_4") (pintype "passive"))
      (node (ref "X28") (pin "49") (pinfunction "49_49") (pintype "passive"))
    )
    (net (code "262") (name "Net-(K76B--)") (class "Default")
      (node (ref "K76") (pin "2") (pinfunction "-_2") (pintype "passive"))
      (node (ref "Q81") (pin "3") (pinfunction "D_3") (pintype "passive"))
    )
    (net (code "263") (name "Net-(K77A-CA)") (class "Default")
      (node (ref "K77") (pin "3") (pinfunction "CA_3") (pintype "passive"))
      (node (ref "X30") (pin "50") (pinfunction "50_50") (pintype "passive"))
    )
    (net (code "264") (name "Net-(K77A-CB)") (class "Default")
      (node (ref "K77") (pin "4") (pinfunction "CB_4") (pintype "passive"))
      (node (ref "X28") (pin "50") (pinfunction "50_50") (pintype "passive"))
    )
    (net (code "265") (name "Net-(K77B--)") (class "Default")
      (node (ref "K77") (pin "2") (pinfunction "-_2") (pintype "passive"))
      (node (ref "Q82") (pin "3") (pinfunction "D_3") (pintype "passive"))
    )
    (net (code "266") (name "Net-(K78A-CA)") (class "Default")
      (node (ref "K78") (pin "3") (pinfunction "CA_3") (pintype "passive"))
      (node (ref "X30") (pin "51") (pinfunction "51_51") (pintype "passive"))
    )
    (net (code "267") (name "Net-(K78A-CB)") (class "Default")
      (node (ref "K78") (pin "4") (pinfunction "CB_4") (pintype "passive"))
      (node (ref "X28") (pin "51") (pinfunction "51_51") (pintype "passive"))
    )
    (net (code "268") (name "Net-(K78B--)") (class "Default")
      (node (ref "K78") (pin "2") (pinfunction "-_2") (pintype "passive"))
      (node (ref "Q83") (pin "3") (pinfunction "D_3") (pintype "passive"))
    )
    (net (code "269") (name "Net-(K79A-CA)") (class "Default")
      (node (ref "K79") (pin "3") (pinfunction "CA_3") (pintype "passive"))
      (node (ref "X30") (pin "52") (pinfunction "52_52") (pintype "passive"))
    )
    (net (code "270") (name "Net-(K79A-CB)") (class "Default")
      (node (ref "K79") (pin "4") (pinfunction "CB_4") (pintype "passive"))
      (node (ref "X28") (pin "52") (pinfunction "52_52") (pintype "passive"))
    )
    (net (code "271") (name "Net-(K79B--)") (class "Default")
      (node (ref "K79") (pin "2") (pinfunction "-_2") (pintype "passive"))
      (node (ref "Q84") (pin "3") (pinfunction "D_3") (pintype "passive"))
    )
    (net (code "272") (name "Net-(K80A-CA)") (class "Default")
      (node (ref "K80") (pin "3") (pinfunction "CA_3") (pintype "passive"))
      (node (ref "X30") (pin "53") (pinfunction "53_53") (pintype "passive"))
    )
    (net (code "273") (name "Net-(K80A-CB)") (class "Default")
      (node (ref "K80") (pin "4") (pinfunction "CB_4") (pintype "passive"))
      (node (ref "X28") (pin "53") (pinfunction "53_53") (pintype "passive"))
    )
    (net (code "274") (name "Net-(K80B--)") (class "Default")
      (node (ref "K80") (pin "2") (pinfunction "-_2") (pintype "passive"))
      (node (ref "Q85") (pin "3") (pinfunction "D_3") (pintype "passive"))
    )
    (net (code "275") (name "Net-(K81A-CA)") (class "Default")
      (node (ref "K81") (pin "3") (pinfunction "CA_3") (pintype "passive"))
      (node (ref "X30") (pin "54") (pinfunction "54_54") (pintype "passive"))
    )
    (net (code "276") (name "Net-(K81A-CB)") (class "Default")
      (node (ref "K81") (pin "4") (pinfunction "CB_4") (pintype "passive"))
      (node (ref "X28") (pin "54") (pinfunction "54_54") (pintype "passive"))
    )
    (net (code "277") (name "Net-(K81B--)") (class "Default")
      (node (ref "K81") (pin "2") (pinfunction "-_2") (pintype "passive"))
      (node (ref "Q86") (pin "3") (pinfunction "D_3") (pintype "passive"))
    )
    (net (code "278") (name "Net-(K82A-CA)") (class "Default")
      (node (ref "K82") (pin "3") (pinfunction "CA_3") (pintype "passive"))
      (node (ref "X30") (pin "55") (pinfunction "55_55") (pintype "passive"))
    )
    (net (code "279") (name "Net-(K82A-CB)") (class "Default")
      (node (ref "K82") (pin "4") (pinfunction "CB_4") (pintype "passive"))
      (node (ref "X28") (pin "55") (pinfunction "55_55") (pintype "passive"))
    )
    (net (code "280") (name "Net-(K82B--)") (class "Default")
      (node (ref "K82") (pin "2") (pinfunction "-_2") (pintype "passive"))
      (node (ref "Q87") (pin "3") (pinfunction "D_3") (pintype "passive"))
    )
    (net (code "281") (name "Net-(K83A-CA)") (class "Default")
      (node (ref "K83") (pin "3") (pinfunction "CA_3") (pintype "passive"))
      (node (ref "X30") (pin "56") (pinfunction "56_56") (pintype "passive"))
    )
    (net (code "282") (name "Net-(K83A-CB)") (class "Default")
      (node (ref "K83") (pin "4") (pinfunction "CB_4") (pintype "passive"))
      (node (ref "X28") (pin "56") (pinfunction "56_56") (pintype "passive"))
    )
    (net (code "283") (name "Net-(K83B--)") (class "Default")
      (node (ref "K83") (pin "2") (pinfunction "-_2") (pintype "passive"))
      (node (ref "Q88") (pin "3") (pinfunction "D_3") (pintype "passive"))
    )
    (net (code "284") (name "Net-(K84A-CA)") (class "Default")
      (node (ref "K84") (pin "3") (pinfunction "CA_3") (pintype "passive"))
      (node (ref "X30") (pin "57") (pinfunction "57_57") (pintype "passive"))
    )
    (net (code "285") (name "Net-(K84A-CB)") (class "Default")
      (node (ref "K84") (pin "4") (pinfunction "CB_4") (pintype "passive"))
      (node (ref "X28") (pin "57") (pinfunction "57_57") (pintype "passive"))
    )
    (net (code "286") (name "Net-(K84B--)") (class "Default")
      (node (ref "K84") (pin "2") (pinfunction "-_2") (pintype "passive"))
      (node (ref "Q89") (pin "3") (pinfunction "D_3") (pintype "passive"))
    )
    (net (code "287") (name "Net-(K85A-CA)") (class "Default")
      (node (ref "K85") (pin "3") (pinfunction "CA_3") (pintype "passive"))
      (node (ref "X30") (pin "58") (pinfunction "58_58") (pintype "passive"))
    )
    (net (code "288") (name "Net-(K85A-CB)") (class "Default")
      (node (ref "K85") (pin "4") (pinfunction "CB_4") (pintype "passive"))
      (node (ref "X28") (pin "58") (pinfunction "58_58") (pintype "passive"))
    )
    (net (code "289") (name "Net-(K85B--)") (class "Default")
      (node (ref "K85") (pin "2") (pinfunction "-_2") (pintype "passive"))
      (node (ref "Q90") (pin "3") (pinfunction "D_3") (pintype "passive"))
    )
    (net (code "290") (name "Net-(K86A-CA)") (class "Default")
      (node (ref "K86") (pin "3") (pinfunction "CA_3") (pintype "passive"))
      (node (ref "X30") (pin "59") (pinfunction "59_59") (pintype "passive"))
    )
    (net (code "291") (name "Net-(K86A-CB)") (class "Default")
      (node (ref "K86") (pin "4") (pinfunction "CB_4") (pintype "passive"))
      (node (ref "X28") (pin "59") (pinfunction "59_59") (pintype "passive"))
    )
    (net (code "292") (name "Net-(K86B--)") (class "Default")
      (node (ref "K86") (pin "2") (pinfunction "-_2") (pintype "passive"))
      (node (ref "Q91") (pin "3") (pinfunction "D_3") (pintype "passive"))
    )
    (net (code "293") (name "Net-(K87A-CA)") (class "Default")
      (node (ref "K87") (pin "3") (pinfunction "CA_3") (pintype "passive"))
      (node (ref "X30") (pin "60") (pinfunction "60_60") (pintype "passive"))
    )
    (net (code "294") (name "Net-(K87A-CB)") (class "Default")
      (node (ref "K87") (pin "4") (pinfunction "CB_4") (pintype "passive"))
      (node (ref "X28") (pin "60") (pinfunction "60_60") (pintype "passive"))
    )
    (net (code "295") (name "Net-(K87B--)") (class "Default")
      (node (ref "K87") (pin "2") (pinfunction "-_2") (pintype "passive"))
      (node (ref "Q92") (pin "3") (pinfunction "D_3") (pintype "passive"))
    )
    (net (code "296") (name "Net-(K88A-CA)") (class "Default")
      (node (ref "K88") (pin "3") (pinfunction "CA_3") (pintype "passive"))
      (node (ref "X30") (pin "61") (pinfunction "61_61") (pintype "passive"))
    )
    (net (code "297") (name "Net-(K88A-CB)") (class "Default")
      (node (ref "K88") (pin "4") (pinfunction "CB_4") (pintype "passive"))
      (node (ref "X28") (pin "61") (pinfunction "61_61") (pintype "passive"))
    )
    (net (code "298") (name "Net-(K88B--)") (class "Default")
      (node (ref "K88") (pin "2") (pinfunction "-_2") (pintype "passive"))
      (node (ref "Q93") (pin "3") (pinfunction "D_3") (pintype "passive"))
    )
    (net (code "299") (name "Net-(K89A-CA)") (class "Default")
      (node (ref "K89") (pin "3") (pinfunction "CA_3") (pintype "passive"))
      (node (ref "X30") (pin "62") (pinfunction "62_62") (pintype "passive"))
    )
    (net (code "300") (name "Net-(K89A-CB)") (class "Default")
      (node (ref "K89") (pin "4") (pinfunction "CB_4") (pintype "passive"))
      (node (ref "X28") (pin "62") (pinfunction "62_62") (pintype "passive"))
    )
    (net (code "301") (name "Net-(K89B--)") (class "Default")
      (node (ref "K89") (pin "2") (pinfunction "-_2") (pintype "passive"))
      (node (ref "Q94") (pin "3") (pinfunction "D_3") (pintype "passive"))
    )
    (net (code "302") (name "Net-(K90A-CA)") (class "Default")
      (node (ref "K90") (pin "3") (pinfunction "CA_3") (pintype "passive"))
      (node (ref "X30") (pin "63") (pinfunction "63_63") (pintype "passive"))
    )
    (net (code "303") (name "Net-(K90A-CB)") (class "Default")
      (node (ref "K90") (pin "4") (pinfunction "CB_4") (pintype "passive"))
      (node (ref "X28") (pin "63") (pinfunction "63_63") (pintype "passive"))
    )
    (net (code "304") (name "Net-(K90B--)") (class "Default")
      (node (ref "K90") (pin "2") (pinfunction "-_2") (pintype "passive"))
      (node (ref "Q95") (pin "3") (pinfunction "D_3") (pintype "passive"))
    )
    (net (code "305") (name "Net-(K91A-CA)") (class "Default")
      (node (ref "K91") (pin "3") (pinfunction "CA_3") (pintype "passive"))
      (node (ref "X30") (pin "64") (pinfunction "64_64") (pintype "passive"))
    )
    (net (code "306") (name "Net-(K91A-CB)") (class "Default")
      (node (ref "K91") (pin "4") (pinfunction "CB_4") (pintype "passive"))
      (node (ref "X28") (pin "64") (pinfunction "64_64") (pintype "passive"))
    )
    (net (code "307") (name "Net-(K91B--)") (class "Default")
      (node (ref "K91") (pin "2") (pinfunction "-_2") (pintype "passive"))
      (node (ref "Q96") (pin "3") (pinfunction "D_3") (pintype "passive"))
    )
  )
)
